# Sheet1.net
KiCad netlist of a schematic drawn in Altium Designer
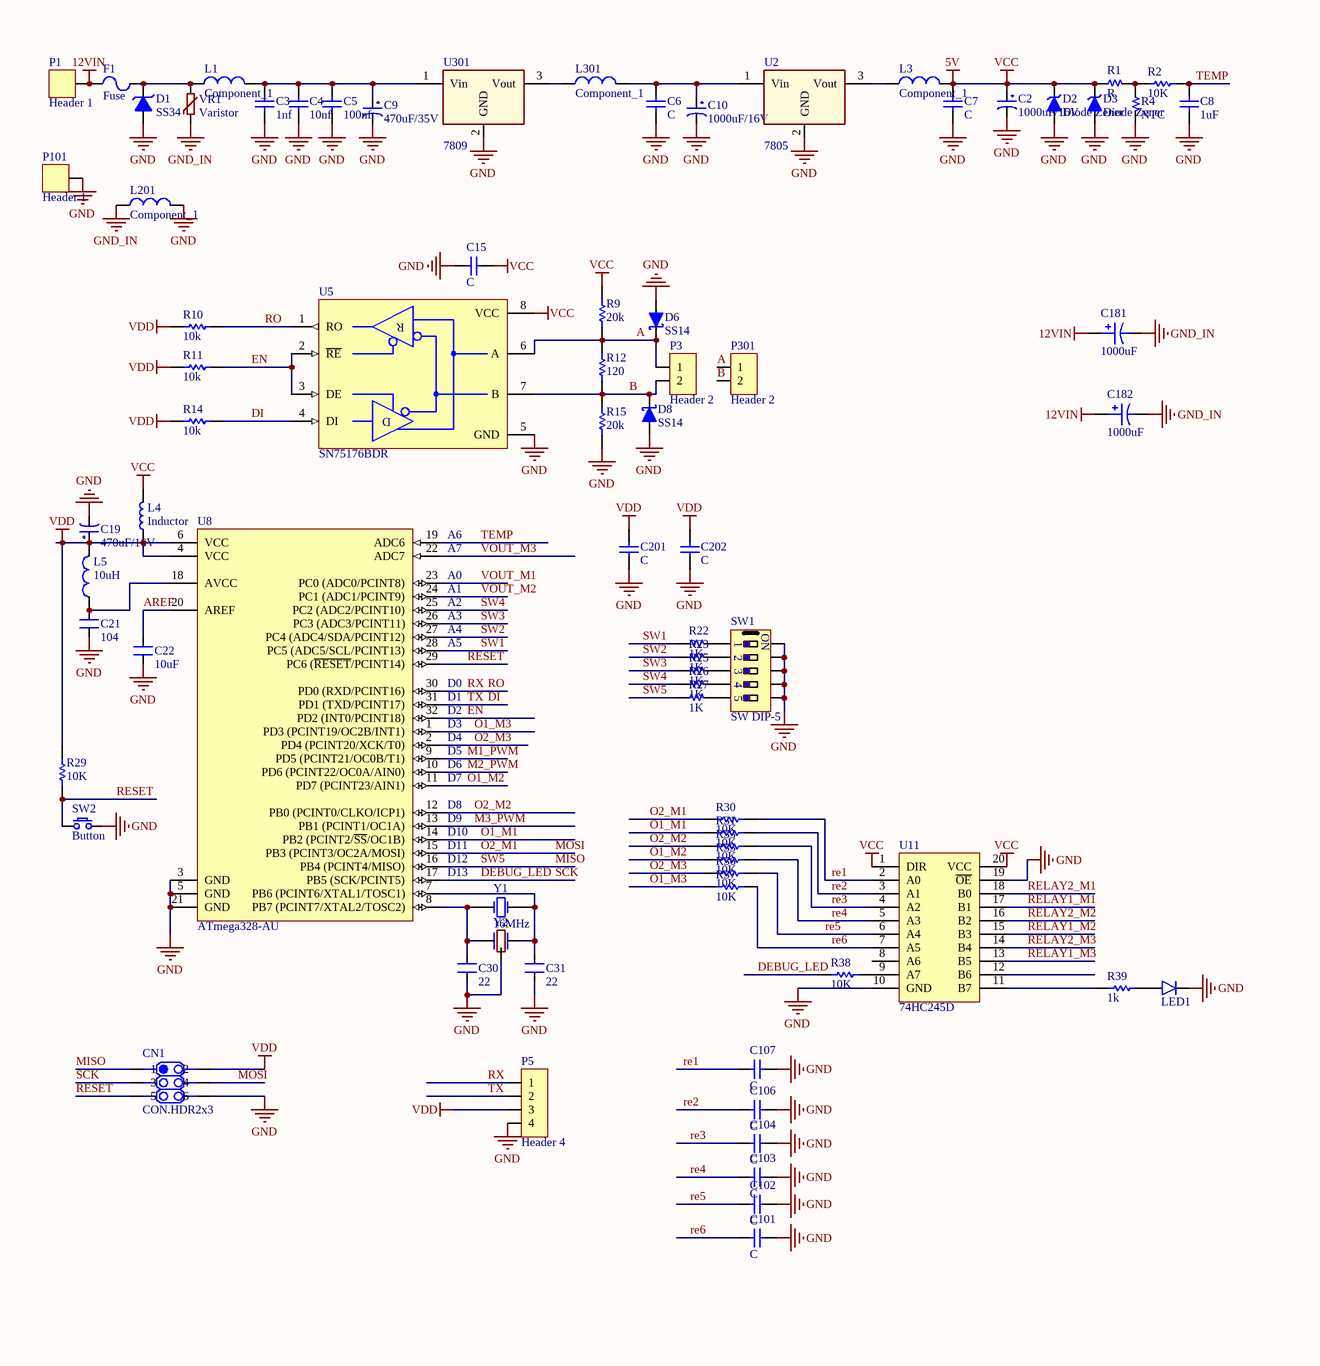
[diagram p0: Sheet1.SchDoc, left]
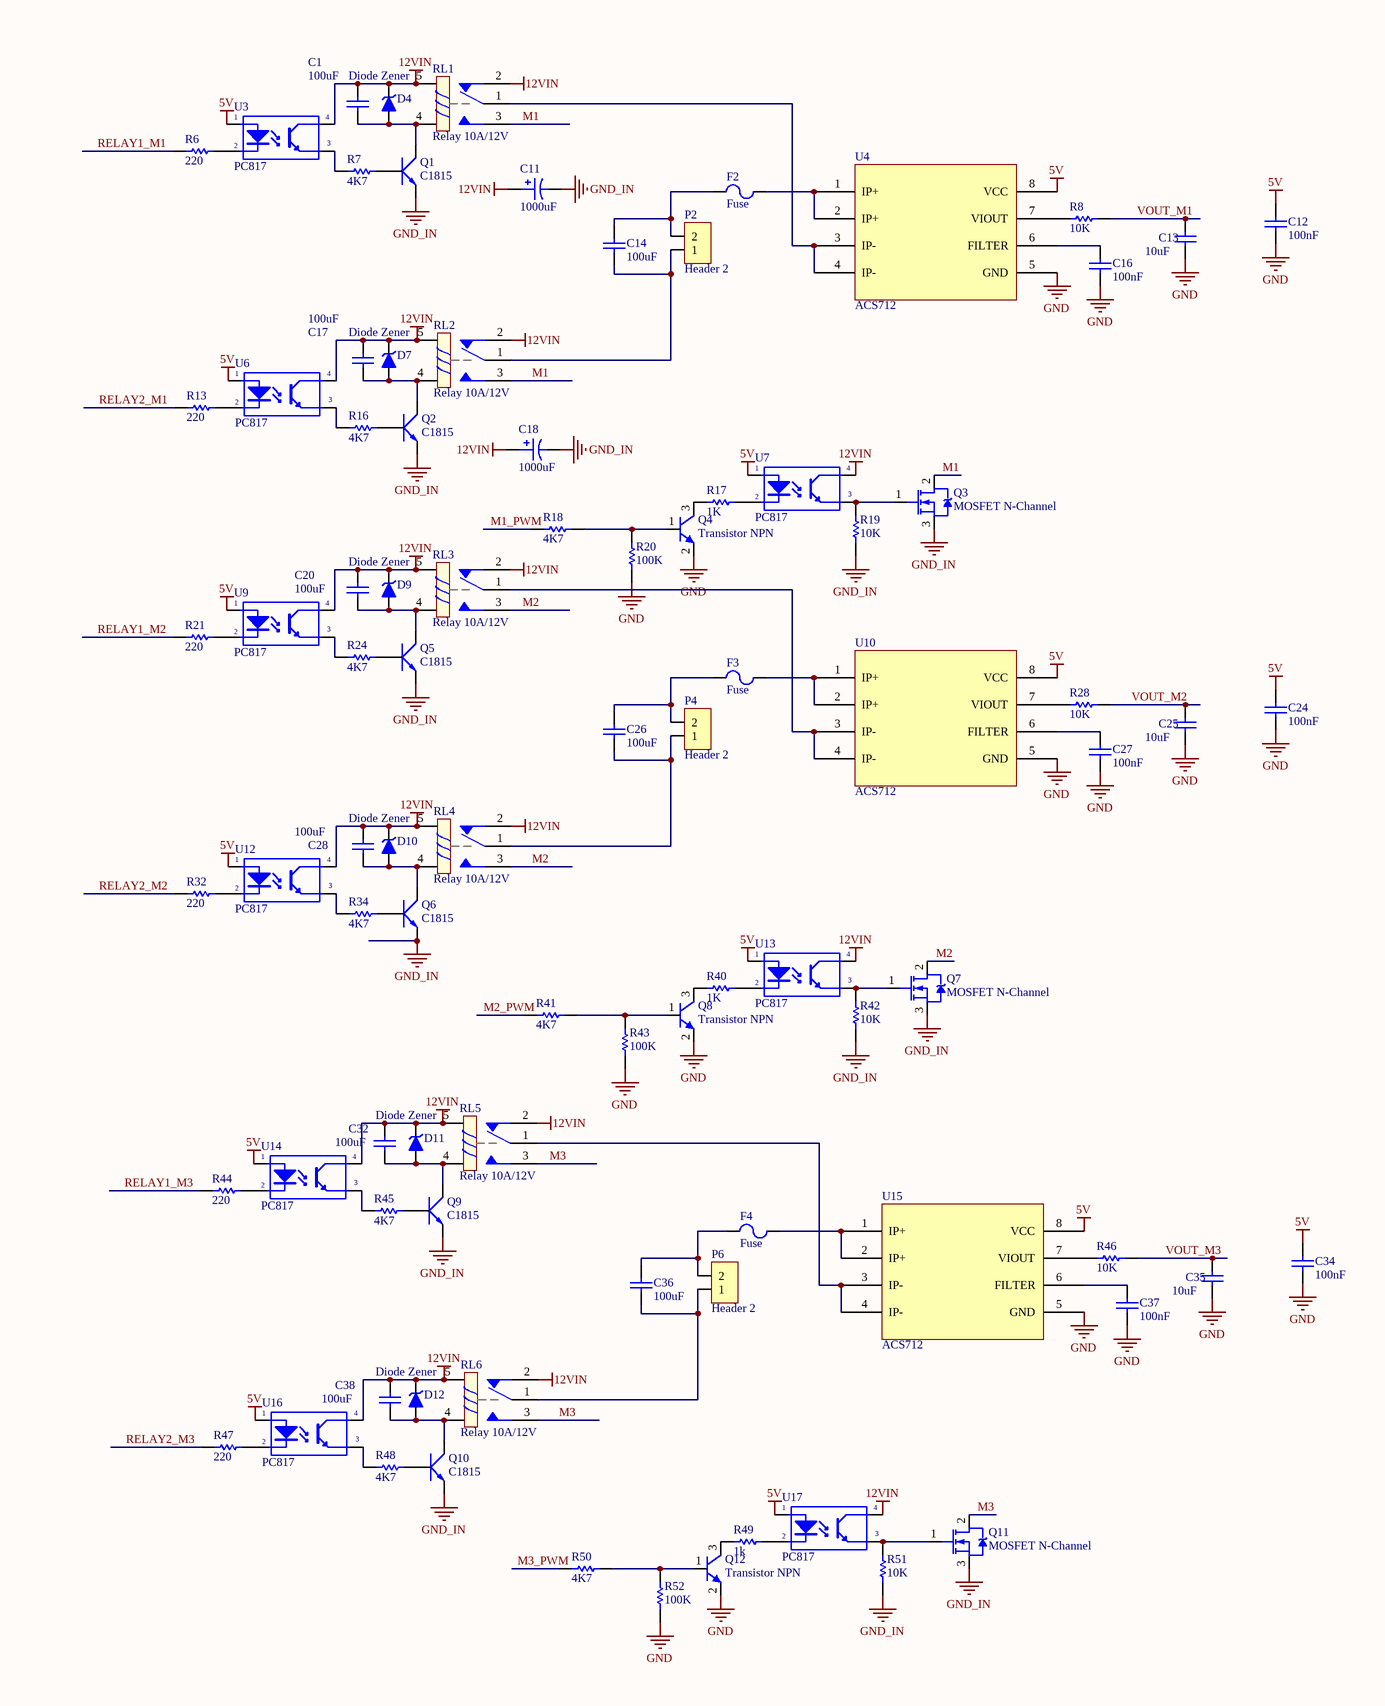
[diagram p1: Sheet1.SchDoc, right]

(export (version "E")
  (design (tool "Eeschema 10.0.6"))
  (components
    (comp (ref "C1")
      (value "100uF")
      (footprint "C 0805 (2012)")
      (description "Non-polarized Capacitor")
      (fields (field (name "Comment") "Cap Non-pol") (field (name "PUBLISHER") "Altium Limited"))
      (libsource (lib "phong") (part "Cap Non-pol"))
    )
    (comp (ref "C2")
      (value "1000uF/16V")
      (footprint "WCAP-PSHP 8x8.7x3.1")
      (description "Cap 1000uF/16V - 220uF/50V")
      (libsource (lib "syhaunguyen") (part "CP4"))
    )
    (comp (ref "C3")
      (value "1nf")
      (footprint "C 0805 (2012)")
      (description "Capacitor non-pol")
      (libsource (lib "BKIT4U_LIB") (part "Capacitor NP"))
    )
    (comp (ref "C4")
      (value "10nf")
      (footprint "C 0805 (2012)")
      (description "Capacitor non-pol")
      (libsource (lib "BKIT4U_LIB") (part "Capacitor NP"))
    )
    (comp (ref "C5")
      (value "100nf")
      (footprint "C 0805 (2012)")
      (description "Capacitor non-pol")
      (libsource (lib "BKIT4U_LIB") (part "Capacitor NP"))
    )
    (comp (ref "C6")
      (value "C")
      (footprint "C 0805 (2012)")
      (description "Capacitor non-pol")
      (libsource (lib "BKIT4U_LIB") (part "Capacitor NP"))
    )
    (comp (ref "C7")
      (value "C")
      (footprint "C 0805 (2012)")
      (description "Capacitor non-pol")
      (libsource (lib "BKIT4U_LIB") (part "Capacitor NP"))
    )
    (comp (ref "C8")
      (value "1uF")
      (footprint "C 0805 (2012)")
      (description "Capacitor non-pol")
      (libsource (lib "BKIT4U_LIB") (part "Capacitor NP"))
    )
    (comp (ref "C9")
      (value "470uF/35V")
      (footprint "WCAP-PSHP 8x8.7x3.1")
      (description "Cap 100uF/35V - 470uF/16V")
      (libsource (lib "syhaunguyen") (part "CP3"))
    )
    (comp (ref "C10")
      (value "1000uF/16V")
      (footprint "WCAP-PSHP 8x8.7x3.1")
      (description "Cap 1000uF/16V - 220uF/50V")
      (libsource (lib "syhaunguyen") (part "CP4"))
    )
    (comp (ref "C11")
      (value "1000uF")
      (footprint "RADIAL E")
      (description "Polarized Capacitor")
      (fields (field (name "Comment") "Cap Pol") (field (name "PUBLISHER") "Altium Limited"))
      (libsource (lib "phong") (part "Cap Pol"))
    )
    (comp (ref "C12")
      (value "100nF")
      (footprint "C 0805 (2012)")
      (description "Non-polarized Capacitor")
      (fields (field (name "Comment") "Cap Non-pol") (field (name "PUBLISHER") "Altium Limited"))
      (libsource (lib "phong") (part "Cap Non-pol"))
    )
    (comp (ref "C13")
      (value "10uF")
      (footprint "C 0805 (2012)")
      (description "Non-polarized Capacitor")
      (fields (field (name "Comment") "Cap Non-pol") (field (name "PUBLISHER") "Altium Limited"))
      (libsource (lib "phong") (part "Cap Non-pol"))
    )
    (comp (ref "C14")
      (value "100uF")
      (footprint "Cap Non-Pol 5mm")
      (description "Non-polarized Capacitor")
      (fields (field (name "Comment") "Cap Non-pol") (field (name "PUBLISHER") "Altium Limited"))
      (libsource (lib "phong") (part "Cap Non-pol"))
    )
    (comp (ref "C15")
      (value "C")
      (footprint "C 0805 (2012)")
      (description "Capacitor non-pol")
      (libsource (lib "BKIT4U_LIB") (part "Capacitor NP"))
    )
    (comp (ref "C16")
      (value "100nF")
      (footprint "C 0805 (2012)")
      (description "Non-polarized Capacitor")
      (fields (field (name "Comment") "Cap Non-pol") (field (name "PUBLISHER") "Altium Limited"))
      (libsource (lib "phong") (part "Cap Non-pol"))
    )
    (comp (ref "C17")
      (value "100uF")
      (footprint "C 0805 (2012)")
      (description "Non-polarized Capacitor")
      (fields (field (name "Comment") "Cap Non-pol") (field (name "PUBLISHER") "Altium Limited"))
      (libsource (lib "phong") (part "Cap Non-pol"))
    )
    (comp (ref "C18")
      (value "1000uF")
      (footprint "RADIAL E")
      (description "Polarized Capacitor")
      (fields (field (name "Comment") "Cap Pol") (field (name "PUBLISHER") "Altium Limited"))
      (libsource (lib "phong") (part "Cap Pol"))
    )
    (comp (ref "C19")
      (value "470uF/16V")
      (footprint "WCAP-PSHP 8x8.7x3.1")
      (description "Cap 1000uF/16V - 220uF/50V")
      (libsource (lib "syhaunguyen") (part "CP4"))
    )
    (comp (ref "C20")
      (value "100uF")
      (footprint "C 0805 (2012)")
      (description "Non-polarized Capacitor")
      (fields (field (name "Comment") "Cap Non-pol") (field (name "PUBLISHER") "Altium Limited"))
      (libsource (lib "phong") (part "Cap Non-pol"))
    )
    (comp (ref "C21")
      (value "104")
      (footprint "R 0805 (2012)")
      (description "Cap np 104 => 105pF")
      (libsource (lib "syhaunguyen") (part "CN2"))
    )
    (comp (ref "C22")
      (value "10uF")
      (footprint "R 0805 (2012)")
      (description "Cap np  1pF - 472pF")
      (libsource (lib "syhaunguyen") (part "CN1"))
    )
    (comp (ref "C24")
      (value "100nF")
      (footprint "C 0805 (2012)")
      (description "Non-polarized Capacitor")
      (fields (field (name "Comment") "Cap Non-pol") (field (name "PUBLISHER") "Altium Limited"))
      (libsource (lib "phong") (part "Cap Non-pol"))
    )
    (comp (ref "C25")
      (value "10uF")
      (footprint "C 0805 (2012)")
      (description "Non-polarized Capacitor")
      (fields (field (name "Comment") "Cap Non-pol") (field (name "PUBLISHER") "Altium Limited"))
      (libsource (lib "phong") (part "Cap Non-pol"))
    )
    (comp (ref "C26")
      (value "100uF")
      (footprint "Cap Non-Pol 5mm")
      (description "Non-polarized Capacitor")
      (fields (field (name "Comment") "Cap Non-pol") (field (name "PUBLISHER") "Altium Limited"))
      (libsource (lib "phong") (part "Cap Non-pol"))
    )
    (comp (ref "C27")
      (value "100nF")
      (footprint "C 0805 (2012)")
      (description "Non-polarized Capacitor")
      (fields (field (name "Comment") "Cap Non-pol") (field (name "PUBLISHER") "Altium Limited"))
      (libsource (lib "phong") (part "Cap Non-pol"))
    )
    (comp (ref "C28")
      (value "100uF")
      (footprint "C 0805 (2012)")
      (description "Non-polarized Capacitor")
      (fields (field (name "Comment") "Cap Non-pol") (field (name "PUBLISHER") "Altium Limited"))
      (libsource (lib "phong") (part "Cap Non-pol"))
    )
    (comp (ref "C30")
      (value "22")
      (footprint "C 0805 (2012)")
      (description "Cap np 104 => 105pF")
      (libsource (lib "syhaunguyen") (part "CN2"))
    )
    (comp (ref "C31")
      (value "22")
      (footprint "C 0805 (2012)")
      (description "Cap np 104 => 105pF")
      (libsource (lib "syhaunguyen") (part "CN2"))
    )
    (comp (ref "C32")
      (value "100uF")
      (footprint "C 0805 (2012)")
      (description "Non-polarized Capacitor")
      (fields (field (name "Comment") "Cap Non-pol") (field (name "PUBLISHER") "Altium Limited"))
      (libsource (lib "phong") (part "Cap Non-pol"))
    )
    (comp (ref "C34")
      (value "100nF")
      (footprint "Cap Non-Pol 5mm")
      (description "Non-polarized Capacitor")
      (fields (field (name "Comment") "Cap Non-pol") (field (name "PUBLISHER") "Altium Limited"))
      (libsource (lib "phong") (part "Cap Non-pol"))
    )
    (comp (ref "C35")
      (value "10uF")
      (footprint "C 0805 (2012)")
      (description "Non-polarized Capacitor")
      (fields (field (name "Comment") "Cap Non-pol") (field (name "PUBLISHER") "Altium Limited"))
      (libsource (lib "phong") (part "Cap Non-pol"))
    )
    (comp (ref "C36")
      (value "100uF")
      (footprint "Cap Non-Pol 5mm")
      (description "Non-polarized Capacitor")
      (fields (field (name "Comment") "Cap Non-pol") (field (name "PUBLISHER") "Altium Limited"))
      (libsource (lib "phong") (part "Cap Non-pol"))
    )
    (comp (ref "C37")
      (value "100nF")
      (footprint "C 0805 (2012)")
      (description "Non-polarized Capacitor")
      (fields (field (name "Comment") "Cap Non-pol") (field (name "PUBLISHER") "Altium Limited"))
      (libsource (lib "phong") (part "Cap Non-pol"))
    )
    (comp (ref "C38")
      (value "100uF")
      (footprint "C 0805 (2012)")
      (description "Non-polarized Capacitor")
      (fields (field (name "Comment") "Cap Non-pol") (field (name "PUBLISHER") "Altium Limited"))
      (libsource (lib "phong") (part "Cap Non-pol"))
    )
    (comp (ref "C101")
      (value "C")
      (footprint "C 0805")
      (description "Capacitor non-pol")
      (libsource (lib "chipfc_altium_libs") (part "Capacitor NP"))
    )
    (comp (ref "C102")
      (value "C")
      (footprint "C 0805")
      (description "Capacitor non-pol")
      (libsource (lib "chipfc_altium_libs") (part "Capacitor NP"))
    )
    (comp (ref "C103")
      (value "C")
      (footprint "C 0805")
      (description "Capacitor non-pol")
      (libsource (lib "chipfc_altium_libs") (part "Capacitor NP"))
    )
    (comp (ref "C104")
      (value "C")
      (footprint "C 0805")
      (description "Capacitor non-pol")
      (libsource (lib "chipfc_altium_libs") (part "Capacitor NP"))
    )
    (comp (ref "C106")
      (value "C")
      (footprint "C 0805")
      (description "Capacitor non-pol")
      (libsource (lib "chipfc_altium_libs") (part "Capacitor NP"))
    )
    (comp (ref "C107")
      (value "C")
      (footprint "C 0805")
      (description "Capacitor non-pol")
      (libsource (lib "chipfc_altium_libs") (part "Capacitor NP"))
    )
    (comp (ref "C181")
      (value "1000uF")
      (footprint "RADIAL E")
      (description "Polarized Capacitor")
      (fields (field (name "Comment") "Cap Pol") (field (name "PUBLISHER") "Altium Limited"))
      (libsource (lib "phong") (part "Cap Pol"))
    )
    (comp (ref "C182")
      (value "1000uF")
      (footprint "RADIAL E")
      (description "Polarized Capacitor")
      (fields (field (name "Comment") "Cap Pol") (field (name "PUBLISHER") "Altium Limited"))
      (libsource (lib "phong") (part "Cap Pol"))
    )
    (comp (ref "C201")
      (value "C")
      (footprint "C 0805 (2012)")
      (description "Capacitor non-pol")
      (libsource (lib "BKIT4U_LIB") (part "Capacitor NP"))
    )
    (comp (ref "C202")
      (value "C")
      (footprint "C 0805 (2012)")
      (description "Capacitor non-pol")
      (libsource (lib "BKIT4U_LIB") (part "Capacitor NP"))
    )
    (comp (ref "CN1")
      (value "CON.HDR2x3")
      (footprint "Header 3x2")
      (description "Header 2x3")
      (fields (field (name "PUBLISHER") "Hoang Nguyen"))
      (libsource (lib "phong") (part "CON.HDR2x3"))
    )
    (comp (ref "D1")
      (value "SS34")
      (footprint "DO-214AC (SMA)")
      (libsource (lib "syhaunguyen") (part "Zener"))
    )
    (comp (ref "D2")
      (value "Diode Zener")
      (footprint "SOD-80")
      (description "Zener Diode")
      (fields (field (name "PUBLISHER") "Altium Limited"))
      (libsource (lib "BKIT4U_LIB") (part "Diode Zener"))
    )
    (comp (ref "D3")
      (value "Diode Zener")
      (footprint "SOD-80")
      (description "Zener Diode")
      (fields (field (name "PUBLISHER") "Altium Limited"))
      (libsource (lib "BKIT4U_LIB") (part "Diode Zener"))
    )
    (comp (ref "D4")
      (value "Diode Zener")
      (footprint "SOD-80")
      (description "Zener Diode")
      (fields (field (name "PUBLISHER") "Altium Limited"))
      (libsource (lib "BKIT4U_LIB") (part "Diode Zener"))
    )
    (comp (ref "D6")
      (value "SS14")
      (footprint "DO-214AC (SMA)")
      (description "Schottky Diode")
      (fields (field (name "PUBLISHER") "Altium Limited"))
      (libsource (lib "BKIT4U_LIB") (part "Diode Schottky"))
    )
    (comp (ref "D7")
      (value "Diode Zener")
      (footprint "SOD-80")
      (description "Zener Diode")
      (fields (field (name "PUBLISHER") "Altium Limited"))
      (libsource (lib "BKIT4U_LIB") (part "Diode Zener"))
    )
    (comp (ref "D8")
      (value "SS14")
      (footprint "DO-214AC (SMA)")
      (description "Schottky Diode")
      (fields (field (name "PUBLISHER") "Altium Limited"))
      (libsource (lib "BKIT4U_LIB") (part "Diode Schottky"))
    )
    (comp (ref "D9")
      (value "Diode Zener")
      (footprint "SOD-80")
      (description "Zener Diode")
      (fields (field (name "PUBLISHER") "Altium Limited"))
      (libsource (lib "BKIT4U_LIB") (part "Diode Zener"))
    )
    (comp (ref "D10")
      (value "Diode Zener")
      (footprint "SOD-80")
      (description "Zener Diode")
      (fields (field (name "PUBLISHER") "Altium Limited"))
      (libsource (lib "BKIT4U_LIB") (part "Diode Zener"))
    )
    (comp (ref "D11")
      (value "Diode Zener")
      (footprint "SOD-80")
      (description "Zener Diode")
      (fields (field (name "PUBLISHER") "Altium Limited"))
      (libsource (lib "BKIT4U_LIB") (part "Diode Zener"))
    )
    (comp (ref "D12")
      (value "Diode Zener")
      (footprint "SOD-80")
      (description "Zener Diode")
      (fields (field (name "PUBLISHER") "Altium Limited"))
      (libsource (lib "BKIT4U_LIB") (part "Diode Zener"))
    )
    (comp (ref "F1")
      (value "Fuse")
      (footprint "FUSE 4 DIP")
      (libsource (lib "chipfc_altium_libs") (part "Fuse"))
    )
    (comp (ref "F2")
      (value "Fuse")
      (footprint "FUSE 4 DIP")
      (libsource (lib "chipfc_altium_libs") (part "Fuse"))
    )
    (comp (ref "F3")
      (value "Fuse")
      (footprint "FUSE 4 DIP")
      (libsource (lib "chipfc_altium_libs") (part "Fuse"))
    )
    (comp (ref "F4")
      (value "Fuse")
      (footprint "FUSE 4 DIP")
      (libsource (lib "chipfc_altium_libs") (part "Fuse"))
    )
    (comp (ref "L1")
      (value "Component_1")
      (footprint "1210")
      (libsource (lib "Integrated_Library1") (part "Component_1"))
    )
    (comp (ref "L3")
      (value "Component_1")
      (footprint "1210")
      (libsource (lib "Integrated_Library1") (part "Component_1"))
    )
    (comp (ref "L4")
      (value "Inductor")
      (footprint "Inductor SMD 4.8x4.8")
      (libsource (lib "BKIT4U_LIB") (part "Inductor"))
    )
    (comp (ref "L5")
      (value "10uH")
      (footprint "R 0805 (2012)")
      (description "Inductor")
      (libsource (lib "syhaunguyen") (part "L1"))
    )
    (comp (ref "L201")
      (value "Component_1")
      (footprint "1210")
      (libsource (lib "Integrated_Library1") (part "Component_1"))
    )
    (comp (ref "L301")
      (value "Component_1")
      (footprint "1210")
      (libsource (lib "Integrated_Library1") (part "Component_1"))
    )
    (comp (ref "LED1")
      (value "Led")
      (footprint "Led SMD 0805")
      (description "Typical LED")
      (libsource (lib "BKIT4U_LIB") (part "Led"))
    )
    (comp (ref "P1")
      (value "Header 1")
      (footprint "HDR/Terminal/1/copper/8.8")
      (description "Header, 1-Pin")
      (libsource (lib "chipfc_altium_libs") (part "Header 1"))
    )
    (comp (ref "P2")
      (value "Header 2")
      (footprint "HDR Domino 2")
      (description "Header, 2-Pin")
      (fields (field (name "PUBLISHER") "Altium Limited"))
      (libsource (lib "BKIT4U_LIB") (part "Header 2"))
    )
    (comp (ref "P3")
      (value "Header 2")
      (footprint "HDR Domino 2")
      (description "Header, 2-Pin")
      (fields (field (name "PUBLISHER") "Altium Limited"))
      (libsource (lib "") (part "Header 2_1"))
    )
    (comp (ref "P4")
      (value "Header 2")
      (footprint "HDR Domino 2")
      (description "Header, 2-Pin")
      (fields (field (name "PUBLISHER") "Altium Limited"))
      (libsource (lib "BKIT4U_LIB") (part "Header 2"))
    )
    (comp (ref "P5")
      (value "Header 4")
      (footprint "Header 4")
      (description "Header, 4-Pin")
      (libsource (lib "BKIT4U_LIB") (part "Header 4"))
    )
    (comp (ref "P6")
      (value "Header 2")
      (footprint "HDR Domino 2")
      (description "Header, 2-Pin")
      (fields (field (name "PUBLISHER") "Altium Limited"))
      (libsource (lib "BKIT4U_LIB") (part "Header 2"))
    )
    (comp (ref "P101")
      (value "Header 1")
      (footprint "HDR/Terminal/1/copper/8.8")
      (description "Header, 1-Pin")
      (libsource (lib "chipfc_altium_libs") (part "Header 1"))
    )
    (comp (ref "P301")
      (value "Header 2")
      (footprint "HDR Domino 2")
      (description "Header, 2-Pin")
      (fields (field (name "PUBLISHER") "Altium Limited"))
      (libsource (lib "") (part "Header 2_1"))
    )
    (comp (ref "Q1")
      (value "C1815")
      (footprint "SOT23B")
      (description "NPN 600mW, ECB")
      (libsource (lib "syhaunguyen") (part "C1815"))
    )
    (comp (ref "Q2")
      (value "C1815")
      (footprint "SOT23B")
      (description "NPN 600mW, ECB")
      (libsource (lib "syhaunguyen") (part "C1815"))
    )
    (comp (ref "Q3")
      (value "MOSFET N-Channel")
      (footprint "TO-252 (DPAK)")
      (libsource (lib "BKIT4U_LIB") (part "MOSFET N-Channel"))
    )
    (comp (ref "Q4")
      (value "Transistor NPN")
      (footprint "SOT-23")
      (description "NPN Bipolar Transistor")
      (libsource (lib "BKIT4U_LIB") (part "Transistor NPN"))
    )
    (comp (ref "Q5")
      (value "C1815")
      (footprint "SOT23B")
      (description "NPN 600mW, ECB")
      (libsource (lib "syhaunguyen") (part "C1815"))
    )
    (comp (ref "Q6")
      (value "C1815")
      (footprint "SOT23B")
      (description "NPN 600mW, ECB")
      (libsource (lib "syhaunguyen") (part "C1815"))
    )
    (comp (ref "Q7")
      (value "MOSFET N-Channel")
      (footprint "TO-252 (DPAK)")
      (libsource (lib "BKIT4U_LIB") (part "MOSFET N-Channel"))
    )
    (comp (ref "Q8")
      (value "Transistor NPN")
      (footprint "SOT-23")
      (description "NPN Bipolar Transistor")
      (libsource (lib "BKIT4U_LIB") (part "Transistor NPN"))
    )
    (comp (ref "Q9")
      (value "C1815")
      (footprint "SOT23B")
      (description "NPN 600mW, ECB")
      (libsource (lib "syhaunguyen") (part "C1815"))
    )
    (comp (ref "Q10")
      (value "C1815")
      (footprint "SOT23B")
      (description "NPN 600mW, ECB")
      (libsource (lib "syhaunguyen") (part "C1815"))
    )
    (comp (ref "Q11")
      (value "MOSFET N-Channel")
      (footprint "TO-252 (DPAK)")
      (libsource (lib "BKIT4U_LIB") (part "MOSFET N-Channel"))
    )
    (comp (ref "Q12")
      (value "Transistor NPN")
      (footprint "SOT-23")
      (description "NPN Bipolar Transistor")
      (libsource (lib "BKIT4U_LIB") (part "Transistor NPN"))
    )
    (comp (ref "R1")
      (value "R")
      (footprint "R 0805")
      (description "Resistor")
      (libsource (lib "chipfc_altium_libs") (part "Resistor"))
    )
    (comp (ref "R2")
      (value "10K")
      (footprint "R 0805 (2012)")
      (description "Resistor")
      (fields (field (name "PUBLISHER") "Altium Limited"))
      (libsource (lib "BKIT4U_LIB") (part "Resistor"))
    )
    (comp (ref "R4")
      (value "NTC")
      (footprint "R 1/4W/300")
      (description "Resistor")
      (libsource (lib "chipfc_altium_libs") (part "Resistor"))
    )
    (comp (ref "R6")
      (value "220")
      (footprint "R 0805 (2012)")
      (description "Resistor")
      (fields (field (name "PUBLISHER") "Altium Limited"))
      (libsource (lib "BKIT4U_LIB") (part "Resistor"))
    )
    (comp (ref "R7")
      (value "4K7")
      (footprint "R 0805 (2012)")
      (description "Resistor")
      (fields (field (name "PUBLISHER") "Altium Limited"))
      (libsource (lib "BKIT4U_LIB") (part "Resistor"))
    )
    (comp (ref "R8")
      (value "10K")
      (footprint "R 0805 (2012)")
      (description "Resistor")
      (fields (field (name "PUBLISHER") "Altium Limited"))
      (libsource (lib "BKIT4U_LIB") (part "Resistor"))
    )
    (comp (ref "R9")
      (value "20k")
      (footprint "R 0805 (2012)")
      (description "Resistor")
      (fields (field (name "PUBLISHER") "Altium Limited"))
      (libsource (lib "BKIT4U_LIB") (part "Resistor"))
    )
    (comp (ref "R10")
      (value "10k")
      (footprint "R 0805 (2012)")
      (description "Resistor")
      (fields (field (name "PUBLISHER") "Altium Limited"))
      (libsource (lib "BKIT4U_LIB") (part "Resistor"))
    )
    (comp (ref "R11")
      (value "10k")
      (footprint "R 0805 (2012)")
      (description "Resistor")
      (fields (field (name "PUBLISHER") "Altium Limited"))
      (libsource (lib "BKIT4U_LIB") (part "Resistor"))
    )
    (comp (ref "R12")
      (value "120")
      (footprint "R 0805 (2012)")
      (description "Resistor")
      (fields (field (name "PUBLISHER") "Altium Limited"))
      (libsource (lib "BKIT4U_LIB") (part "Resistor"))
    )
    (comp (ref "R13")
      (value "220")
      (footprint "R 0805 (2012)")
      (description "Resistor")
      (fields (field (name "PUBLISHER") "Altium Limited"))
      (libsource (lib "BKIT4U_LIB") (part "Resistor"))
    )
    (comp (ref "R14")
      (value "10k")
      (footprint "R 0805 (2012)")
      (description "Resistor")
      (fields (field (name "PUBLISHER") "Altium Limited"))
      (libsource (lib "BKIT4U_LIB") (part "Resistor"))
    )
    (comp (ref "R15")
      (value "20k")
      (footprint "R 0805 (2012)")
      (description "Resistor")
      (fields (field (name "PUBLISHER") "Altium Limited"))
      (libsource (lib "BKIT4U_LIB") (part "Resistor"))
    )
    (comp (ref "R16")
      (value "4K7")
      (footprint "R 0805 (2012)")
      (description "Resistor")
      (fields (field (name "PUBLISHER") "Altium Limited"))
      (libsource (lib "BKIT4U_LIB") (part "Resistor"))
    )
    (comp (ref "R17")
      (value "1K")
      (footprint "R 0805 (2012)")
      (description "Resistor")
      (fields (field (name "PUBLISHER") "Altium Limited"))
      (libsource (lib "BKIT4U_LIB") (part "Resistor"))
    )
    (comp (ref "R18")
      (value "4K7")
      (footprint "R 0805 (2012)")
      (description "Resistor")
      (fields (field (name "PUBLISHER") "Altium Limited"))
      (libsource (lib "BKIT4U_LIB") (part "Resistor"))
    )
    (comp (ref "R19")
      (value "10K")
      (footprint "R 0805 (2012)")
      (description "Resistor")
      (fields (field (name "PUBLISHER") "Altium Limited"))
      (libsource (lib "BKIT4U_LIB") (part "Resistor"))
    )
    (comp (ref "R20")
      (value "100K")
      (footprint "R 0805 (2012)")
      (description "Resistor")
      (fields (field (name "PUBLISHER") "Altium Limited"))
      (libsource (lib "BKIT4U_LIB") (part "Resistor"))
    )
    (comp (ref "R21")
      (value "220")
      (footprint "R 0805 (2012)")
      (description "Resistor")
      (fields (field (name "PUBLISHER") "Altium Limited"))
      (libsource (lib "BKIT4U_LIB") (part "Resistor"))
    )
    (comp (ref "R22")
      (value "1K")
      (footprint "R 0805")
      (description "Resistor")
      (libsource (lib "chipfc_altium_libs") (part "Resistor"))
    )
    (comp (ref "R23")
      (value "1K")
      (footprint "R 0805")
      (description "Resistor")
      (libsource (lib "chipfc_altium_libs") (part "Resistor"))
    )
    (comp (ref "R24")
      (value "4K7")
      (footprint "R 0805 (2012)")
      (description "Resistor")
      (fields (field (name "PUBLISHER") "Altium Limited"))
      (libsource (lib "BKIT4U_LIB") (part "Resistor"))
    )
    (comp (ref "R25")
      (value "1K")
      (footprint "R 0805")
      (description "Resistor")
      (libsource (lib "chipfc_altium_libs") (part "Resistor"))
    )
    (comp (ref "R26")
      (value "1K")
      (footprint "R 0805")
      (description "Resistor")
      (libsource (lib "chipfc_altium_libs") (part "Resistor"))
    )
    (comp (ref "R27")
      (value "1K")
      (footprint "R 0805")
      (description "Resistor")
      (libsource (lib "chipfc_altium_libs") (part "Resistor"))
    )
    (comp (ref "R28")
      (value "10K")
      (footprint "R 0805 (2012)")
      (description "Resistor")
      (fields (field (name "PUBLISHER") "Altium Limited"))
      (libsource (lib "BKIT4U_LIB") (part "Resistor"))
    )
    (comp (ref "R29")
      (value "10K")
      (footprint "R 0805 (2012)")
      (description "Resistor")
      (fields (field (name "PUBLISHER") "Altium Limited"))
      (libsource (lib "phong") (part "Resistor"))
    )
    (comp (ref "R30")
      (value "10K")
      (footprint "R 0805 (2012)")
      (description "Resistor")
      (fields (field (name "PUBLISHER") "Altium Limited"))
      (libsource (lib "BKIT4U_LIB") (part "Resistor"))
    )
    (comp (ref "R31")
      (value "10K")
      (footprint "R 0805 (2012)")
      (description "Resistor")
      (fields (field (name "PUBLISHER") "Altium Limited"))
      (libsource (lib "BKIT4U_LIB") (part "Resistor"))
    )
    (comp (ref "R32")
      (value "220")
      (footprint "R 0805 (2012)")
      (description "Resistor")
      (fields (field (name "PUBLISHER") "Altium Limited"))
      (libsource (lib "BKIT4U_LIB") (part "Resistor"))
    )
    (comp (ref "R33")
      (value "10K")
      (footprint "R 0805 (2012)")
      (description "Resistor")
      (fields (field (name "PUBLISHER") "Altium Limited"))
      (libsource (lib "BKIT4U_LIB") (part "Resistor"))
    )
    (comp (ref "R34")
      (value "4K7")
      (footprint "R 0805 (2012)")
      (description "Resistor")
      (fields (field (name "PUBLISHER") "Altium Limited"))
      (libsource (lib "BKIT4U_LIB") (part "Resistor"))
    )
    (comp (ref "R35")
      (value "10K")
      (footprint "R 0805 (2012)")
      (description "Resistor")
      (fields (field (name "PUBLISHER") "Altium Limited"))
      (libsource (lib "BKIT4U_LIB") (part "Resistor"))
    )
    (comp (ref "R36")
      (value "10K")
      (footprint "R 0805 (2012)")
      (description "Resistor")
      (fields (field (name "PUBLISHER") "Altium Limited"))
      (libsource (lib "BKIT4U_LIB") (part "Resistor"))
    )
    (comp (ref "R37")
      (value "10K")
      (footprint "R 0805 (2012)")
      (description "Resistor")
      (fields (field (name "PUBLISHER") "Altium Limited"))
      (libsource (lib "BKIT4U_LIB") (part "Resistor"))
    )
    (comp (ref "R38")
      (value "10K")
      (footprint "R 0805 (2012)")
      (description "Resistor")
      (fields (field (name "PUBLISHER") "Altium Limited"))
      (libsource (lib "BKIT4U_LIB") (part "Resistor"))
    )
    (comp (ref "R39")
      (value "1k")
      (footprint "R 0805 (2012)")
      (description "Resistor")
      (fields (field (name "PUBLISHER") "Altium Limited"))
      (libsource (lib "BKIT4U_LIB") (part "Resistor"))
    )
    (comp (ref "R40")
      (value "1K")
      (footprint "R 0805 (2012)")
      (description "Resistor")
      (fields (field (name "PUBLISHER") "Altium Limited"))
      (libsource (lib "BKIT4U_LIB") (part "Resistor"))
    )
    (comp (ref "R41")
      (value "4K7")
      (footprint "R 0805 (2012)")
      (description "Resistor")
      (fields (field (name "PUBLISHER") "Altium Limited"))
      (libsource (lib "BKIT4U_LIB") (part "Resistor"))
    )
    (comp (ref "R42")
      (value "10K")
      (footprint "R 0805 (2012)")
      (description "Resistor")
      (fields (field (name "PUBLISHER") "Altium Limited"))
      (libsource (lib "BKIT4U_LIB") (part "Resistor"))
    )
    (comp (ref "R43")
      (value "100K")
      (footprint "R 0805 (2012)")
      (description "Resistor")
      (fields (field (name "PUBLISHER") "Altium Limited"))
      (libsource (lib "BKIT4U_LIB") (part "Resistor"))
    )
    (comp (ref "R44")
      (value "220")
      (footprint "R 0805 (2012)")
      (description "Resistor")
      (fields (field (name "PUBLISHER") "Altium Limited"))
      (libsource (lib "BKIT4U_LIB") (part "Resistor"))
    )
    (comp (ref "R45")
      (value "4K7")
      (footprint "R 0805 (2012)")
      (description "Resistor")
      (fields (field (name "PUBLISHER") "Altium Limited"))
      (libsource (lib "BKIT4U_LIB") (part "Resistor"))
    )
    (comp (ref "R46")
      (value "10K")
      (footprint "R 0805 (2012)")
      (description "Resistor")
      (fields (field (name "PUBLISHER") "Altium Limited"))
      (libsource (lib "BKIT4U_LIB") (part "Resistor"))
    )
    (comp (ref "R47")
      (value "220")
      (footprint "R 0805 (2012)")
      (description "Resistor")
      (fields (field (name "PUBLISHER") "Altium Limited"))
      (libsource (lib "BKIT4U_LIB") (part "Resistor"))
    )
    (comp (ref "R48")
      (value "4K7")
      (footprint "R 0805 (2012)")
      (description "Resistor")
      (fields (field (name "PUBLISHER") "Altium Limited"))
      (libsource (lib "BKIT4U_LIB") (part "Resistor"))
    )
    (comp (ref "R49")
      (value "1k")
      (footprint "R 0805 (2012)")
      (description "Resistor")
      (fields (field (name "PUBLISHER") "Altium Limited"))
      (libsource (lib "BKIT4U_LIB") (part "Resistor"))
    )
    (comp (ref "R50")
      (value "4K7")
      (footprint "R 0805 (2012)")
      (description "Resistor")
      (fields (field (name "PUBLISHER") "Altium Limited"))
      (libsource (lib "BKIT4U_LIB") (part "Resistor"))
    )
    (comp (ref "R51")
      (value "10K")
      (footprint "R 0805 (2012)")
      (description "Resistor")
      (fields (field (name "PUBLISHER") "Altium Limited"))
      (libsource (lib "BKIT4U_LIB") (part "Resistor"))
    )
    (comp (ref "R52")
      (value "100K")
      (footprint "R 0805 (2012)")
      (description "Resistor")
      (fields (field (name "PUBLISHER") "Altium Limited"))
      (libsource (lib "BKIT4U_LIB") (part "Resistor"))
    )
    (comp (ref "RL1")
      (value "Relay 10A/12V")
      (footprint "RL_SPDT_10A")
      (description "Relay SPDT,10A - 12VDC 5 Pin")
      (libsource (lib "BKIT4U_LIB") (part "Relay 1"))
    )
    (comp (ref "RL2")
      (value "Relay 10A/12V")
      (footprint "RL_SPDT_10A")
      (description "Relay SPDT,10A - 12VDC 5 Pin")
      (libsource (lib "BKIT4U_LIB") (part "Relay 1"))
    )
    (comp (ref "RL3")
      (value "Relay 10A/12V")
      (footprint "RL_SPDT_10A")
      (description "Relay SPDT,10A - 12VDC 5 Pin")
      (libsource (lib "BKIT4U_LIB") (part "Relay 1"))
    )
    (comp (ref "RL4")
      (value "Relay 10A/12V")
      (footprint "RL_SPDT_10A")
      (description "Relay SPDT,10A - 12VDC 5 Pin")
      (libsource (lib "BKIT4U_LIB") (part "Relay 1"))
    )
    (comp (ref "RL5")
      (value "Relay 10A/12V")
      (footprint "RL_SPDT_10A")
      (description "Relay SPDT,10A - 12VDC 5 Pin")
      (libsource (lib "BKIT4U_LIB") (part "Relay 1"))
    )
    (comp (ref "RL6")
      (value "Relay 10A/12V")
      (footprint "RL_SPDT_10A")
      (description "Relay SPDT,10A - 12VDC 5 Pin")
      (libsource (lib "BKIT4U_LIB") (part "Relay 1"))
    )
    (comp (ref "SW1")
      (value "SW DIP-5")
      (footprint "SW/DIP5/300")
      (libsource (lib "chipfc_altium_libs") (part "SW DIP-5"))
    )
    (comp (ref "SW2")
      (value "Button")
      (footprint "SW/2/SMD")
      (description "Tact switch 2 pin")
      (libsource (lib "BKIT4U_LIB") (part "SW SPST"))
    )
    (comp (ref "U2")
      (value "7805")
      (footprint "TO-252 (DPAK)")
      (description "LDO Fixed Voltage regulator")
      (libsource (lib "BKIT4U_LIB") (part "78xx"))
    )
    (comp (ref "U3")
      (value "PC817")
      (footprint "SOP4 - PC817")
      (description "Single Opto")
      (libsource (lib "syhaunguyen") (part "PC817"))
    )
    (comp (ref "U4") (value "ACS712") (footprint "SO-8 HCPL") (libsource (lib "ACS712") (part "ACS712")))
    (comp (ref "U5") (value "SN75176BDR") (footprint "SOIC-8") (libsource (lib "BKIT4U_LIB") (part "MAX485")))
    (comp (ref "U6")
      (value "PC817")
      (footprint "SOP4 - PC817")
      (description "Single Opto")
      (libsource (lib "syhaunguyen") (part "PC817"))
    )
    (comp (ref "U7")
      (value "PC817")
      (footprint "SOP4 - PC817")
      (description "Single Opto")
      (libsource (lib "syhaunguyen") (part "PC817"))
    )
    (comp (ref "U8")
      (value "ATmega328-AU")
      (footprint "QFP32N")
      (fields (field (name "PUBLISHER") "Altium Limited"))
      (libsource (lib "Atmel Microcontroller 8-Bit megaAVR") (part "ATmega328-AU"))
    )
    (comp (ref "U9")
      (value "PC817")
      (footprint "SOP4 - PC817")
      (description "Single Opto")
      (libsource (lib "syhaunguyen") (part "PC817"))
    )
    (comp (ref "U10") (value "ACS712") (footprint "SO-8 HCPL") (libsource (lib "ACS712") (part "ACS712")))
    (comp (ref "U11")
      (value "74HC245D")
      (footprint "SOIC-20")
      (description "IC TRANSCVR NON-INVERT 6V 20SO")
      (libsource (lib "chipfc_altium_libs") (part "74HC245D"))
    )
    (comp (ref "U12")
      (value "PC817")
      (footprint "SOP4 - PC817")
      (description "Single Opto")
      (libsource (lib "syhaunguyen") (part "PC817"))
    )
    (comp (ref "U13")
      (value "PC817")
      (footprint "SOP4 - PC817")
      (description "Single Opto")
      (libsource (lib "syhaunguyen") (part "PC817"))
    )
    (comp (ref "U14")
      (value "PC817")
      (footprint "SOP4 - PC817")
      (description "Single Opto")
      (libsource (lib "syhaunguyen") (part "PC817"))
    )
    (comp (ref "U15") (value "ACS712") (footprint "SO-8 HCPL") (libsource (lib "ACS712") (part "ACS712")))
    (comp (ref "U16")
      (value "PC817")
      (footprint "SOP4 - PC817")
      (description "Single Opto")
      (libsource (lib "syhaunguyen") (part "PC817"))
    )
    (comp (ref "U17")
      (value "PC817")
      (footprint "SOP4 - PC817")
      (description "Single Opto")
      (libsource (lib "syhaunguyen") (part "PC817"))
    )
    (comp (ref "U301")
      (value "7809")
      (footprint "TO-252 (DPAK)")
      (description "LDO Fixed Voltage regulator")
      (libsource (lib "BKIT4U_LIB") (part "78xx"))
    )
    (comp (ref "VR1")
      (value "Varistor")
      (footprint "VARISTOR DISC 5MM/7MM")
      (libsource (lib "chipfc_altium_libs") (part "Varistor"))
    )
    (comp (ref "Y1")
      (value "16MHz")
      (footprint "XTAL")
      (description "Crystal Oscillator")
      (fields (field (name "PUBLISHER") "Altium Limited"))
      (libsource (lib "phong") (part "XTAL"))
    )
    (comp (ref "Y2")
      (value "~")
      (footprint "Crystal SMD CSTCE")
      (libsource (lib "BKIT4U_LIB") (part "Crystal CSTCE"))
    )
  )
  (nets
    (net (code "1") (name "/A") (class "Default")
      (node (ref "D6") (pin "2") (pinfunction "K_2") (pintype "passive"))
      (node (ref "P3") (pin "1") (pinfunction "1_1") (pintype "passive"))
      (node (ref "P301") (pin "1") (pinfunction "1_1") (pintype "passive"))
      (node (ref "R12") (pin "2") (pinfunction "2_2") (pintype "passive"))
      (node (ref "R9") (pin "1") (pinfunction "1_1") (pintype "passive"))
      (node (ref "U5") (pin "6") (pinfunction "A_6") (pintype "passive"))
    )
    (net (code "2") (name "/AREF") (class "Default")
      (node (ref "C22") (pin "2") (pinfunction "2_2") (pintype "passive"))
      (node (ref "U8") (pin "20") (pinfunction "AREF_20") (pintype "passive"))
    )
    (net (code "3") (name "/B") (class "Default")
      (node (ref "D8") (pin "2") (pinfunction "K_2") (pintype "passive"))
      (node (ref "P3") (pin "2") (pinfunction "2_2") (pintype "passive"))
      (node (ref "P301") (pin "2") (pinfunction "2_2") (pintype "passive"))
      (node (ref "R12") (pin "1") (pinfunction "1_1") (pintype "passive"))
      (node (ref "R15") (pin "2") (pinfunction "2_2") (pintype "passive"))
      (node (ref "U5") (pin "7") (pinfunction "B_7") (pintype "passive"))
    )
    (net (code "4") (name "/DEBUG_LED") (class "Default")
      (node (ref "CN1") (pin "3") (pinfunction "3_3") (pintype "passive"))
      (node (ref "R38") (pin "1") (pinfunction "1_1") (pintype "passive"))
      (node (ref "U8") (pin "17") (pinfunction "PB5_(SCK/PCINT5)_17") (pintype "bidirectional"))
    )
    (net (code "5") (name "/DI") (class "Default")
      (node (ref "P5") (pin "2") (pinfunction "2_2") (pintype "passive"))
      (node (ref "R14") (pin "1") (pinfunction "1_1") (pintype "passive"))
      (node (ref "U5") (pin "4") (pinfunction "DI_4") (pintype "input"))
      (node (ref "U8") (pin "31") (pinfunction "PD1_(TXD/PCINT17)_31") (pintype "bidirectional"))
    )
    (net (code "6") (name "/EN") (class "Default")
      (node (ref "R11") (pin "1") (pinfunction "1_1") (pintype "passive"))
      (node (ref "U5") (pin "2") (pinfunction "~{RE}_2") (pintype "input"))
      (node (ref "U5") (pin "3") (pinfunction "DE_3") (pintype "input"))
      (node (ref "U8") (pin "32") (pinfunction "PD2_(INT0/PCINT18)_32") (pintype "bidirectional"))
    )
    (net (code "7") (name "/M1") (class "Default")
      (node (ref "Q3") (pin "2") (pinfunction "D_2") (pintype "passive"))
      (node (ref "RL1") (pin "3") (pinfunction "3_3") (pintype "passive"))
      (node (ref "RL2") (pin "3") (pinfunction "3_3") (pintype "passive"))
    )
    (net (code "8") (name "/M1_PWM") (class "Default")
      (node (ref "R18") (pin "2") (pinfunction "2_2") (pintype "passive"))
      (node (ref "U8") (pin "9") (pinfunction "PD5_(PCINT21/OC0B/T1)_9") (pintype "bidirectional"))
    )
    (net (code "9") (name "/M2") (class "Default")
      (node (ref "Q7") (pin "2") (pinfunction "D_2") (pintype "passive"))
      (node (ref "RL3") (pin "3") (pinfunction "3_3") (pintype "passive"))
      (node (ref "RL4") (pin "3") (pinfunction "3_3") (pintype "passive"))
    )
    (net (code "10") (name "/M2_PWM") (class "Default")
      (node (ref "R41") (pin "2") (pinfunction "2_2") (pintype "passive"))
      (node (ref "U8") (pin "10") (pinfunction "PD6_(PCINT22/OC0A/AIN0)_10") (pintype "bidirectional"))
    )
    (net (code "11") (name "/M3") (class "Default")
      (node (ref "Q11") (pin "2") (pinfunction "D_2") (pintype "passive"))
      (node (ref "RL5") (pin "3") (pinfunction "3_3") (pintype "passive"))
      (node (ref "RL6") (pin "3") (pinfunction "3_3") (pintype "passive"))
    )
    (net (code "12") (name "/M3_PWM") (class "Default")
      (node (ref "R50") (pin "2") (pinfunction "2_2") (pintype "passive"))
      (node (ref "U8") (pin "13") (pinfunction "PB1_(PCINT1/OC1A)_13") (pintype "bidirectional"))
    )
    (net (code "13") (name "/MISO") (class "Default")
      (node (ref "CN1") (pin "1") (pinfunction "1_1") (pintype "passive"))
      (node (ref "R27") (pin "1") (pinfunction "1_1") (pintype "passive"))
      (node (ref "U8") (pin "16") (pinfunction "PB4_(PCINT4/MISO)_16") (pintype "bidirectional"))
    )
    (net (code "14") (name "/MOSI") (class "Default")
      (node (ref "CN1") (pin "4") (pinfunction "4_4") (pintype "passive"))
      (node (ref "R30") (pin "1") (pinfunction "1_1") (pintype "passive"))
      (node (ref "U8") (pin "15") (pinfunction "PB3_(PCINT3/OC2A/MOSI)_15") (pintype "bidirectional"))
    )
    (net (code "15") (name "/O1_M1") (class "Default")
      (node (ref "R31") (pin "1") (pinfunction "1_1") (pintype "passive"))
      (node (ref "U8") (pin "14") (pinfunction "PB2_(PCINT2/~{SS}/OC1B)_14") (pintype "bidirectional"))
    )
    (net (code "16") (name "/O1_M2") (class "Default")
      (node (ref "R35") (pin "1") (pinfunction "1_1") (pintype "passive"))
      (node (ref "U8") (pin "11") (pinfunction "PD7_(PCINT23/AIN1)_11") (pintype "bidirectional"))
    )
    (net (code "17") (name "/O1_M3") (class "Default")
      (node (ref "R37") (pin "1") (pinfunction "1_1") (pintype "passive"))
      (node (ref "U8") (pin "1") (pinfunction "PD3_(PCINT19/OC2B/INT1)_1") (pintype "bidirectional"))
    )
    (net (code "18") (name "/O2_M2") (class "Default")
      (node (ref "R33") (pin "1") (pinfunction "1_1") (pintype "passive"))
      (node (ref "U8") (pin "12") (pinfunction "PB0_(PCINT0/CLKO/ICP1)_12") (pintype "bidirectional"))
    )
    (net (code "19") (name "/O2_M3") (class "Default")
      (node (ref "R36") (pin "1") (pinfunction "1_1") (pintype "passive"))
      (node (ref "U8") (pin "2") (pinfunction "PD4_(PCINT20/XCK/T0)_2") (pintype "bidirectional"))
    )
    (net (code "20") (name "/RELAY1_M1") (class "Default")
      (node (ref "R6") (pin "2") (pinfunction "2_2") (pintype "passive"))
      (node (ref "U11") (pin "17") (pinfunction "B1_17") (pintype "passive"))
    )
    (net (code "21") (name "/RELAY1_M2") (class "Default")
      (node (ref "R21") (pin "2") (pinfunction "2_2") (pintype "passive"))
      (node (ref "U11") (pin "15") (pinfunction "B3_15") (pintype "passive"))
    )
    (net (code "22") (name "/RELAY1_M3") (class "Default")
      (node (ref "R44") (pin "2") (pinfunction "2_2") (pintype "passive"))
      (node (ref "U11") (pin "13") (pinfunction "B5_13") (pintype "passive"))
    )
    (net (code "23") (name "/RELAY2_M1") (class "Default")
      (node (ref "R13") (pin "2") (pinfunction "2_2") (pintype "passive"))
      (node (ref "U11") (pin "18") (pinfunction "B0_18") (pintype "passive"))
    )
    (net (code "24") (name "/RELAY2_M2") (class "Default")
      (node (ref "R32") (pin "2") (pinfunction "2_2") (pintype "passive"))
      (node (ref "U11") (pin "16") (pinfunction "B2_16") (pintype "passive"))
    )
    (net (code "25") (name "/RELAY2_M3") (class "Default")
      (node (ref "R47") (pin "2") (pinfunction "2_2") (pintype "passive"))
      (node (ref "U11") (pin "14") (pinfunction "B4_14") (pintype "passive"))
    )
    (net (code "26") (name "/RESET") (class "Default")
      (node (ref "CN1") (pin "5") (pinfunction "5_5") (pintype "passive"))
      (node (ref "R29") (pin "1") (pinfunction "1_1") (pintype "passive"))
      (node (ref "SW2") (pin "1") (pinfunction "1_1") (pintype "passive"))
      (node (ref "U8") (pin "29") (pinfunction "PC6_(~{RESET}/PCINT14)_29") (pintype "bidirectional"))
    )
    (net (code "27") (name "/RO") (class "Default")
      (node (ref "P5") (pin "1") (pinfunction "1_1") (pintype "passive"))
      (node (ref "R10") (pin "1") (pinfunction "1_1") (pintype "passive"))
      (node (ref "U5") (pin "1") (pinfunction "RO_1") (pintype "output"))
      (node (ref "U8") (pin "30") (pinfunction "PD0_(RXD/PCINT16)_30") (pintype "bidirectional"))
    )
    (net (code "28") (name "/SW1") (class "Default")
      (node (ref "R22") (pin "1") (pinfunction "1_1") (pintype "passive"))
      (node (ref "U8") (pin "28") (pinfunction "PC5_(ADC5/SCL/PCINT13)_28") (pintype "bidirectional"))
    )
    (net (code "29") (name "/SW2") (class "Default")
      (node (ref "R23") (pin "1") (pinfunction "1_1") (pintype "passive"))
      (node (ref "U8") (pin "27") (pinfunction "PC4_(ADC4/SDA/PCINT12)_27") (pintype "bidirectional"))
    )
    (net (code "30") (name "/SW3") (class "Default")
      (node (ref "R25") (pin "1") (pinfunction "1_1") (pintype "passive"))
      (node (ref "U8") (pin "26") (pinfunction "PC3_(ADC3/PCINT11)_26") (pintype "bidirectional"))
    )
    (net (code "31") (name "/SW4") (class "Default")
      (node (ref "R26") (pin "1") (pinfunction "1_1") (pintype "passive"))
      (node (ref "U8") (pin "25") (pinfunction "PC2_(ADC2/PCINT10)_25") (pintype "bidirectional"))
    )
    (net (code "32") (name "/TEMP") (class "Default")
      (node (ref "C8") (pin "1") (pinfunction "1_1") (pintype "passive"))
      (node (ref "R2") (pin "2") (pinfunction "2_2") (pintype "passive"))
      (node (ref "U8") (pin "19") (pinfunction "ADC6_19") (pintype "input"))
    )
    (net (code "33") (name "/VOUT_M1") (class "Default")
      (node (ref "C13") (pin "2") (pinfunction "2_2") (pintype "passive"))
      (node (ref "R8") (pin "2") (pinfunction "2_2") (pintype "passive"))
      (node (ref "U8") (pin "23") (pinfunction "PC0_(ADC0/PCINT8)_23") (pintype "bidirectional"))
    )
    (net (code "34") (name "/VOUT_M2") (class "Default")
      (node (ref "C25") (pin "2") (pinfunction "2_2") (pintype "passive"))
      (node (ref "R28") (pin "2") (pinfunction "2_2") (pintype "passive"))
      (node (ref "U8") (pin "24") (pinfunction "PC1_(ADC1/PCINT9)_24") (pintype "bidirectional"))
    )
    (net (code "35") (name "/VOUT_M3") (class "Default")
      (node (ref "C35") (pin "2") (pinfunction "2_2") (pintype "passive"))
      (node (ref "R46") (pin "2") (pinfunction "2_2") (pintype "passive"))
      (node (ref "U8") (pin "22") (pinfunction "ADC7_22") (pintype "input"))
    )
    (net (code "36") (name "/re1") (class "Default")
      (node (ref "C107") (pin "1") (pinfunction "1_1") (pintype "passive"))
      (node (ref "R30") (pin "2") (pinfunction "2_2") (pintype "passive"))
      (node (ref "U11") (pin "2") (pinfunction "A0_2") (pintype "passive"))
    )
    (net (code "37") (name "/re2") (class "Default")
      (node (ref "C106") (pin "1") (pinfunction "1_1") (pintype "passive"))
      (node (ref "R31") (pin "2") (pinfunction "2_2") (pintype "passive"))
      (node (ref "U11") (pin "3") (pinfunction "A1_3") (pintype "passive"))
    )
    (net (code "38") (name "/re3") (class "Default")
      (node (ref "C104") (pin "1") (pinfunction "1_1") (pintype "passive"))
      (node (ref "R33") (pin "2") (pinfunction "2_2") (pintype "passive"))
      (node (ref "U11") (pin "4") (pinfunction "A2_4") (pintype "passive"))
    )
    (net (code "39") (name "/re4") (class "Default")
      (node (ref "C103") (pin "1") (pinfunction "1_1") (pintype "passive"))
      (node (ref "R35") (pin "2") (pinfunction "2_2") (pintype "passive"))
      (node (ref "U11") (pin "5") (pinfunction "A3_5") (pintype "passive"))
    )
    (net (code "40") (name "/re5") (class "Default")
      (node (ref "C102") (pin "1") (pinfunction "1_1") (pintype "passive"))
      (node (ref "R36") (pin "2") (pinfunction "2_2") (pintype "passive"))
      (node (ref "U11") (pin "6") (pinfunction "A4_6") (pintype "passive"))
    )
    (net (code "41") (name "/re6") (class "Default")
      (node (ref "C101") (pin "1") (pinfunction "1_1") (pintype "passive"))
      (node (ref "R37") (pin "2") (pinfunction "2_2") (pintype "passive"))
      (node (ref "U11") (pin "7") (pinfunction "A5_7") (pintype "passive"))
    )
    (net (code "42") (name "5V") (class "Default")
      (node (ref "C12") (pin "2") (pinfunction "2_2") (pintype "passive"))
      (node (ref "C15") (pin "1") (pinfunction "1_1") (pintype "passive"))
      (node (ref "C2") (pin "1") (pinfunction "1_1") (pintype "passive"))
      (node (ref "C24") (pin "2") (pinfunction "2_2") (pintype "passive"))
      (node (ref "C34") (pin "2") (pinfunction "2_2") (pintype "passive"))
      (node (ref "C7") (pin "1") (pinfunction "1_1") (pintype "passive"))
      (node (ref "D2") (pin "2") (pinfunction "K_2") (pintype "passive"))
      (node (ref "D3") (pin "2") (pinfunction "K_2") (pintype "passive"))
      (node (ref "L3") (pin "2") (pinfunction "2_2") (pintype "passive"))
      (node (ref "L4") (pin "2") (pinfunction "2_2") (pintype "passive"))
      (node (ref "R1") (pin "1") (pinfunction "1_1") (pintype "passive"))
      (node (ref "R9") (pin "2") (pinfunction "2_2") (pintype "passive"))
      (node (ref "U10") (pin "8") (pinfunction "VCC_8") (pintype "passive"))
      (node (ref "U11") (pin "1") (pinfunction "DIR_1") (pintype "passive"))
      (node (ref "U11") (pin "20") (pinfunction "VCC_20") (pintype "passive"))
      (node (ref "U12") (pin "1") (pinfunction "A_1") (pintype "passive"))
      (node (ref "U13") (pin "1") (pinfunction "A_1") (pintype "passive"))
      (node (ref "U14") (pin "1") (pinfunction "A_1") (pintype "passive"))
      (node (ref "U15") (pin "8") (pinfunction "VCC_8") (pintype "passive"))
      (node (ref "U16") (pin "1") (pinfunction "A_1") (pintype "passive"))
      (node (ref "U17") (pin "1") (pinfunction "A_1") (pintype "passive"))
      (node (ref "U3") (pin "1") (pinfunction "A_1") (pintype "passive"))
      (node (ref "U4") (pin "8") (pinfunction "VCC_8") (pintype "passive"))
      (node (ref "U5") (pin "8") (pinfunction "VCC_8") (pintype "passive"))
      (node (ref "U6") (pin "1") (pinfunction "A_1") (pintype "passive"))
      (node (ref "U7") (pin "1") (pinfunction "A_1") (pintype "passive"))
      (node (ref "U9") (pin "1") (pinfunction "A_1") (pintype "passive"))
    )
    (net (code "43") (name "12VIN") (class "Default")
      (node (ref "C1") (pin "2") (pinfunction "2_2") (pintype "passive"))
      (node (ref "C11") (pin "1") (pinfunction "1_1") (pintype "passive"))
      (node (ref "C17") (pin "2") (pinfunction "2_2") (pintype "passive"))
      (node (ref "C18") (pin "1") (pinfunction "1_1") (pintype "passive"))
      (node (ref "C181") (pin "1") (pinfunction "1_1") (pintype "passive"))
      (node (ref "C182") (pin "1") (pinfunction "1_1") (pintype "passive"))
      (node (ref "C20") (pin "2") (pinfunction "2_2") (pintype "passive"))
      (node (ref "C28") (pin "2") (pinfunction "2_2") (pintype "passive"))
      (node (ref "C32") (pin "2") (pinfunction "2_2") (pintype "passive"))
      (node (ref "C38") (pin "2") (pinfunction "2_2") (pintype "passive"))
      (node (ref "D10") (pin "2") (pinfunction "K_2") (pintype "passive"))
      (node (ref "D11") (pin "2") (pinfunction "K_2") (pintype "passive"))
      (node (ref "D12") (pin "2") (pinfunction "K_2") (pintype "passive"))
      (node (ref "D4") (pin "2") (pinfunction "K_2") (pintype "passive"))
      (node (ref "D7") (pin "2") (pinfunction "K_2") (pintype "passive"))
      (node (ref "D9") (pin "2") (pinfunction "K_2") (pintype "passive"))
      (node (ref "F1") (pin "1") (pinfunction "1_1") (pintype "passive"))
      (node (ref "P1") (pin "1") (pinfunction "1_1") (pintype "passive"))
      (node (ref "RL1") (pin "2") (pinfunction "2_2") (pintype "passive"))
      (node (ref "RL1") (pin "5") (pinfunction "5_5") (pintype "passive"))
      (node (ref "RL2") (pin "2") (pinfunction "2_2") (pintype "passive"))
      (node (ref "RL2") (pin "5") (pinfunction "5_5") (pintype "passive"))
      (node (ref "RL3") (pin "2") (pinfunction "2_2") (pintype "passive"))
      (node (ref "RL3") (pin "5") (pinfunction "5_5") (pintype "passive"))
      (node (ref "RL4") (pin "2") (pinfunction "2_2") (pintype "passive"))
      (node (ref "RL4") (pin "5") (pinfunction "5_5") (pintype "passive"))
      (node (ref "RL5") (pin "2") (pinfunction "2_2") (pintype "passive"))
      (node (ref "RL5") (pin "5") (pinfunction "5_5") (pintype "passive"))
      (node (ref "RL6") (pin "2") (pinfunction "2_2") (pintype "passive"))
      (node (ref "RL6") (pin "5") (pinfunction "5_5") (pintype "passive"))
      (node (ref "U12") (pin "4") (pinfunction "C_4") (pintype "passive"))
      (node (ref "U13") (pin "4") (pinfunction "C_4") (pintype "passive"))
      (node (ref "U14") (pin "4") (pinfunction "C_4") (pintype "passive"))
      (node (ref "U16") (pin "4") (pinfunction "C_4") (pintype "passive"))
      (node (ref "U17") (pin "4") (pinfunction "C_4") (pintype "passive"))
      (node (ref "U3") (pin "4") (pinfunction "C_4") (pintype "passive"))
      (node (ref "U6") (pin "4") (pinfunction "C_4") (pintype "passive"))
      (node (ref "U7") (pin "4") (pinfunction "C_4") (pintype "passive"))
      (node (ref "U9") (pin "4") (pinfunction "C_4") (pintype "passive"))
    )
    (net (code "44") (name "GND") (class "Default")
      (node (ref "C10") (pin "2") (pinfunction "2_2") (pintype "passive"))
      (node (ref "C101") (pin "2") (pinfunction "2_2") (pintype "passive"))
      (node (ref "C102") (pin "2") (pinfunction "2_2") (pintype "passive"))
      (node (ref "C103") (pin "2") (pinfunction "2_2") (pintype "passive"))
      (node (ref "C104") (pin "2") (pinfunction "2_2") (pintype "passive"))
      (node (ref "C106") (pin "2") (pinfunction "2_2") (pintype "passive"))
      (node (ref "C107") (pin "2") (pinfunction "2_2") (pintype "passive"))
      (node (ref "C12") (pin "1") (pinfunction "1_1") (pintype "passive"))
      (node (ref "C13") (pin "1") (pinfunction "1_1") (pintype "passive"))
      (node (ref "C15") (pin "2") (pinfunction "2_2") (pintype "passive"))
      (node (ref "C16") (pin "1") (pinfunction "1_1") (pintype "passive"))
      (node (ref "C19") (pin "2") (pinfunction "2_2") (pintype "passive"))
      (node (ref "C2") (pin "2") (pinfunction "2_2") (pintype "passive"))
      (node (ref "C201") (pin "2") (pinfunction "2_2") (pintype "passive"))
      (node (ref "C202") (pin "2") (pinfunction "2_2") (pintype "passive"))
      (node (ref "C21") (pin "1") (pinfunction "1_1") (pintype "passive"))
      (node (ref "C22") (pin "1") (pinfunction "1_1") (pintype "passive"))
      (node (ref "C24") (pin "1") (pinfunction "1_1") (pintype "passive"))
      (node (ref "C25") (pin "1") (pinfunction "1_1") (pintype "passive"))
      (node (ref "C27") (pin "1") (pinfunction "1_1") (pintype "passive"))
      (node (ref "C3") (pin "2") (pinfunction "2_2") (pintype "passive"))
      (node (ref "C30") (pin "1") (pinfunction "1_1") (pintype "passive"))
      (node (ref "C31") (pin "1") (pinfunction "1_1") (pintype "passive"))
      (node (ref "C34") (pin "1") (pinfunction "1_1") (pintype "passive"))
      (node (ref "C35") (pin "1") (pinfunction "1_1") (pintype "passive"))
      (node (ref "C37") (pin "1") (pinfunction "1_1") (pintype "passive"))
      (node (ref "C4") (pin "2") (pinfunction "2_2") (pintype "passive"))
      (node (ref "C5") (pin "2") (pinfunction "2_2") (pintype "passive"))
      (node (ref "C6") (pin "2") (pinfunction "2_2") (pintype "passive"))
      (node (ref "C7") (pin "2") (pinfunction "2_2") (pintype "passive"))
      (node (ref "C8") (pin "2") (pinfunction "2_2") (pintype "passive"))
      (node (ref "C9") (pin "2") (pinfunction "2_2") (pintype "passive"))
      (node (ref "CN1") (pin "6") (pinfunction "6_6") (pintype "passive"))
      (node (ref "D1") (pin "1") (pinfunction "A_1") (pintype "passive"))
      (node (ref "D2") (pin "1") (pinfunction "A_1") (pintype "passive"))
      (node (ref "D3") (pin "1") (pinfunction "A_1") (pintype "passive"))
      (node (ref "D6") (pin "1") (pinfunction "A_1") (pintype "passive"))
      (node (ref "D8") (pin "1") (pinfunction "A_1") (pintype "passive"))
      (node (ref "L201") (pin "2") (pinfunction "2_2") (pintype "passive"))
      (node (ref "LED1") (pin "2") (pinfunction "K_2") (pintype "passive"))
      (node (ref "P101") (pin "1") (pinfunction "1_1") (pintype "passive"))
      (node (ref "P5") (pin "4") (pinfunction "4_4") (pintype "passive"))
      (node (ref "Q12") (pin "2") (pinfunction "E_2") (pintype "passive"))
      (node (ref "Q4") (pin "2") (pinfunction "E_2") (pintype "passive"))
      (node (ref "Q8") (pin "2") (pinfunction "E_2") (pintype "passive"))
      (node (ref "R15") (pin "1") (pinfunction "1_1") (pintype "passive"))
      (node (ref "R20") (pin "1") (pinfunction "1_1") (pintype "passive"))
      (node (ref "R4") (pin "2") (pinfunction "2_2") (pintype "passive"))
      (node (ref "R43") (pin "1") (pinfunction "1_1") (pintype "passive"))
      (node (ref "R52") (pin "1") (pinfunction "1_1") (pintype "passive"))
      (node (ref "SW1") (pin "10") (pinfunction "10_10") (pintype "passive"))
      (node (ref "SW1") (pin "6") (pinfunction "6_6") (pintype "passive"))
      (node (ref "SW1") (pin "7") (pinfunction "7_7") (pintype "passive"))
      (node (ref "SW1") (pin "8") (pinfunction "8_8") (pintype "passive"))
      (node (ref "SW1") (pin "9") (pinfunction "9_9") (pintype "passive"))
      (node (ref "SW2") (pin "2") (pinfunction "2_2") (pintype "passive"))
      (node (ref "U10") (pin "5") (pinfunction "GND_5") (pintype "passive"))
      (node (ref "U11") (pin "10") (pinfunction "GND_10") (pintype "passive"))
      (node (ref "U11") (pin "19") (pinfunction "~{OE}_19") (pintype "passive"))
      (node (ref "U15") (pin "5") (pinfunction "GND_5") (pintype "passive"))
      (node (ref "U2") (pin "2") (pinfunction "GND_2") (pintype "passive"))
      (node (ref "U301") (pin "2") (pinfunction "GND_2") (pintype "passive"))
      (node (ref "U4") (pin "5") (pinfunction "GND_5") (pintype "passive"))
      (node (ref "U5") (pin "5") (pinfunction "GND_5") (pintype "power_in"))
      (node (ref "U8") (pin "21") (pinfunction "GND_21") (pintype "power_in"))
      (node (ref "U8") (pin "3") (pinfunction "GND_3") (pintype "power_in"))
      (node (ref "U8") (pin "5") (pinfunction "GND_5") (pintype "power_in"))
      (node (ref "Y2") (pin "2") (pinfunction "2_2") (pintype "passive"))
    )
    (net (code "45") (name "GND_IN") (class "Default")
      (node (ref "C11") (pin "2") (pinfunction "2_2") (pintype "passive"))
      (node (ref "C18") (pin "2") (pinfunction "2_2") (pintype "passive"))
      (node (ref "C181") (pin "2") (pinfunction "2_2") (pintype "passive"))
      (node (ref "C182") (pin "2") (pinfunction "2_2") (pintype "passive"))
      (node (ref "L201") (pin "1") (pinfunction "1_1") (pintype "passive"))
      (node (ref "Q1") (pin "1") (pinfunction "E_1") (pintype "passive"))
      (node (ref "Q10") (pin "1") (pinfunction "E_1") (pintype "passive"))
      (node (ref "Q11") (pin "3") (pinfunction "S_3") (pintype "passive"))
      (node (ref "Q2") (pin "1") (pinfunction "E_1") (pintype "passive"))
      (node (ref "Q3") (pin "3") (pinfunction "S_3") (pintype "passive"))
      (node (ref "Q5") (pin "1") (pinfunction "E_1") (pintype "passive"))
      (node (ref "Q6") (pin "1") (pinfunction "E_1") (pintype "passive"))
      (node (ref "Q7") (pin "3") (pinfunction "S_3") (pintype "passive"))
      (node (ref "Q9") (pin "1") (pinfunction "E_1") (pintype "passive"))
      (node (ref "R19") (pin "1") (pinfunction "1_1") (pintype "passive"))
      (node (ref "R42") (pin "2") (pinfunction "2_2") (pintype "passive"))
      (node (ref "R51") (pin "2") (pinfunction "2_2") (pintype "passive"))
      (node (ref "VR1") (pin "2") (pinfunction "2_2") (pintype "passive"))
    )
    (net (code "46") (name "Net-(C14-Pad1)") (class "Default")
      (node (ref "C14") (pin "1") (pinfunction "1_1") (pintype "passive"))
      (node (ref "P2") (pin "1") (pinfunction "1_1") (pintype "passive"))
      (node (ref "RL2") (pin "1") (pinfunction "1_1") (pintype "passive"))
    )
    (net (code "47") (name "Net-(C14-Pad2)") (class "Default")
      (node (ref "C14") (pin "2") (pinfunction "2_2") (pintype "passive"))
      (node (ref "F2") (pin "1") (pinfunction "1_1") (pintype "passive"))
      (node (ref "P2") (pin "2") (pinfunction "2_2") (pintype "passive"))
    )
    (net (code "48") (name "Net-(C26-Pad1)") (class "Default")
      (node (ref "C26") (pin "1") (pinfunction "1_1") (pintype "passive"))
      (node (ref "P4") (pin "1") (pinfunction "1_1") (pintype "passive"))
      (node (ref "RL4") (pin "1") (pinfunction "1_1") (pintype "passive"))
    )
    (net (code "49") (name "Net-(C26-Pad2)") (class "Default")
      (node (ref "C26") (pin "2") (pinfunction "2_2") (pintype "passive"))
      (node (ref "F3") (pin "1") (pinfunction "1_1") (pintype "passive"))
      (node (ref "P4") (pin "2") (pinfunction "2_2") (pintype "passive"))
    )
    (net (code "50") (name "Net-(C36-Pad1)") (class "Default")
      (node (ref "C36") (pin "1") (pinfunction "1_1") (pintype "passive"))
      (node (ref "P6") (pin "1") (pinfunction "1_1") (pintype "passive"))
      (node (ref "RL6") (pin "1") (pinfunction "1_1") (pintype "passive"))
    )
    (net (code "51") (name "Net-(C36-Pad2)") (class "Default")
      (node (ref "C36") (pin "2") (pinfunction "2_2") (pintype "passive"))
      (node (ref "F4") (pin "1") (pinfunction "1_1") (pintype "passive"))
      (node (ref "P6") (pin "2") (pinfunction "2_2") (pintype "passive"))
    )
    (net (code "52") (name "Net-(D1-K)") (class "Default")
      (node (ref "D1") (pin "2") (pinfunction "K_2") (pintype "passive"))
      (node (ref "F1") (pin "2") (pinfunction "2_2") (pintype "passive"))
      (node (ref "L1") (pin "1") (pinfunction "1_1") (pintype "passive"))
      (node (ref "VR1") (pin "1") (pinfunction "1_1") (pintype "passive"))
    )
    (net (code "53") (name "Net-(D4-A)") (class "Default")
      (node (ref "C1") (pin "1") (pinfunction "1_1") (pintype "passive"))
      (node (ref "D4") (pin "1") (pinfunction "A_1") (pintype "passive"))
      (node (ref "Q1") (pin "2") (pinfunction "C_2") (pintype "passive"))
      (node (ref "RL1") (pin "4") (pinfunction "4_4") (pintype "passive"))
    )
    (net (code "54") (name "Net-(D7-A)") (class "Default")
      (node (ref "C17") (pin "1") (pinfunction "1_1") (pintype "passive"))
      (node (ref "D7") (pin "1") (pinfunction "A_1") (pintype "passive"))
      (node (ref "Q2") (pin "2") (pinfunction "C_2") (pintype "passive"))
      (node (ref "RL2") (pin "4") (pinfunction "4_4") (pintype "passive"))
    )
    (net (code "55") (name "Net-(D9-A)") (class "Default")
      (node (ref "C20") (pin "1") (pinfunction "1_1") (pintype "passive"))
      (node (ref "D9") (pin "1") (pinfunction "A_1") (pintype "passive"))
      (node (ref "Q5") (pin "2") (pinfunction "C_2") (pintype "passive"))
      (node (ref "RL3") (pin "4") (pinfunction "4_4") (pintype "passive"))
    )
    (net (code "56") (name "Net-(D10-A)") (class "Default")
      (node (ref "C28") (pin "1") (pinfunction "1_1") (pintype "passive"))
      (node (ref "D10") (pin "1") (pinfunction "A_1") (pintype "passive"))
      (node (ref "Q6") (pin "2") (pinfunction "C_2") (pintype "passive"))
      (node (ref "RL4") (pin "4") (pinfunction "4_4") (pintype "passive"))
    )
    (net (code "57") (name "Net-(D11-A)") (class "Default")
      (node (ref "C32") (pin "1") (pinfunction "1_1") (pintype "passive"))
      (node (ref "D11") (pin "1") (pinfunction "A_1") (pintype "passive"))
      (node (ref "Q9") (pin "2") (pinfunction "C_2") (pintype "passive"))
      (node (ref "RL5") (pin "4") (pinfunction "4_4") (pintype "passive"))
    )
    (net (code "58") (name "Net-(D12-A)") (class "Default")
      (node (ref "C38") (pin "1") (pinfunction "1_1") (pintype "passive"))
      (node (ref "D12") (pin "1") (pinfunction "A_1") (pintype "passive"))
      (node (ref "Q10") (pin "2") (pinfunction "C_2") (pintype "passive"))
      (node (ref "RL6") (pin "4") (pinfunction "4_4") (pintype "passive"))
    )
    (net (code "59") (name "Net-(F2-Pad2)") (class "Default")
      (node (ref "F2") (pin "2") (pinfunction "2_2") (pintype "passive"))
      (node (ref "U4") (pin "1") (pinfunction "IP+_1") (pintype "passive"))
      (node (ref "U4") (pin "2") (pinfunction "IP+_2") (pintype "passive"))
    )
    (net (code "60") (name "Net-(F3-Pad2)") (class "Default")
      (node (ref "F3") (pin "2") (pinfunction "2_2") (pintype "passive"))
      (node (ref "U10") (pin "1") (pinfunction "IP+_1") (pintype "passive"))
      (node (ref "U10") (pin "2") (pinfunction "IP+_2") (pintype "passive"))
    )
    (net (code "61") (name "Net-(F4-Pad2)") (class "Default")
      (node (ref "F4") (pin "2") (pinfunction "2_2") (pintype "passive"))
      (node (ref "U15") (pin "1") (pinfunction "IP+_1") (pintype "passive"))
      (node (ref "U15") (pin "2") (pinfunction "IP+_2") (pintype "passive"))
    )
    (net (code "62") (name "Net-(LED1-A)") (class "Default")
      (node (ref "LED1") (pin "1") (pinfunction "A_1") (pintype "passive"))
      (node (ref "R39") (pin "2") (pinfunction "2_2") (pintype "passive"))
    )
    (net (code "63") (name "Net-(Q1-B)") (class "Default")
      (node (ref "Q1") (pin "3") (pinfunction "B_3") (pintype "passive"))
      (node (ref "R7") (pin "2") (pinfunction "2_2") (pintype "passive"))
    )
    (net (code "64") (name "Net-(Q2-B)") (class "Default")
      (node (ref "Q2") (pin "3") (pinfunction "B_3") (pintype "passive"))
      (node (ref "R16") (pin "2") (pinfunction "2_2") (pintype "passive"))
    )
    (net (code "65") (name "Net-(Q3-G)") (class "Default")
      (node (ref "Q3") (pin "1") (pinfunction "G_1") (pintype "passive"))
      (node (ref "R19") (pin "2") (pinfunction "2_2") (pintype "passive"))
      (node (ref "U7") (pin "3") (pinfunction "E_3") (pintype "passive"))
    )
    (net (code "66") (name "Net-(Q4-B)") (class "Default")
      (node (ref "Q4") (pin "1") (pinfunction "B_1") (pintype "passive"))
      (node (ref "R18") (pin "1") (pinfunction "1_1") (pintype "passive"))
      (node (ref "R20") (pin "2") (pinfunction "2_2") (pintype "passive"))
    )
    (net (code "67") (name "Net-(Q4-C)") (class "Default")
      (node (ref "Q4") (pin "3") (pinfunction "C_3") (pintype "passive"))
      (node (ref "R17") (pin "1") (pinfunction "1_1") (pintype "passive"))
    )
    (net (code "68") (name "Net-(Q5-B)") (class "Default")
      (node (ref "Q5") (pin "3") (pinfunction "B_3") (pintype "passive"))
      (node (ref "R24") (pin "2") (pinfunction "2_2") (pintype "passive"))
    )
    (net (code "69") (name "Net-(Q6-B)") (class "Default")
      (node (ref "Q6") (pin "3") (pinfunction "B_3") (pintype "passive"))
      (node (ref "R34") (pin "2") (pinfunction "2_2") (pintype "passive"))
    )
    (net (code "70") (name "Net-(Q7-G)") (class "Default")
      (node (ref "Q7") (pin "1") (pinfunction "G_1") (pintype "passive"))
      (node (ref "R42") (pin "1") (pinfunction "1_1") (pintype "passive"))
      (node (ref "U13") (pin "3") (pinfunction "E_3") (pintype "passive"))
    )
    (net (code "71") (name "Net-(Q8-B)") (class "Default")
      (node (ref "Q8") (pin "1") (pinfunction "B_1") (pintype "passive"))
      (node (ref "R41") (pin "1") (pinfunction "1_1") (pintype "passive"))
      (node (ref "R43") (pin "2") (pinfunction "2_2") (pintype "passive"))
    )
    (net (code "72") (name "Net-(Q8-C)") (class "Default")
      (node (ref "Q8") (pin "3") (pinfunction "C_3") (pintype "passive"))
      (node (ref "R40") (pin "1") (pinfunction "1_1") (pintype "passive"))
    )
    (net (code "73") (name "Net-(Q9-B)") (class "Default")
      (node (ref "Q9") (pin "3") (pinfunction "B_3") (pintype "passive"))
      (node (ref "R45") (pin "2") (pinfunction "2_2") (pintype "passive"))
    )
    (net (code "74") (name "Net-(Q10-B)") (class "Default")
      (node (ref "Q10") (pin "3") (pinfunction "B_3") (pintype "passive"))
      (node (ref "R48") (pin "2") (pinfunction "2_2") (pintype "passive"))
    )
    (net (code "75") (name "Net-(Q11-G)") (class "Default")
      (node (ref "Q11") (pin "1") (pinfunction "G_1") (pintype "passive"))
      (node (ref "R51") (pin "1") (pinfunction "1_1") (pintype "passive"))
      (node (ref "U17") (pin "3") (pinfunction "E_3") (pintype "passive"))
    )
    (net (code "76") (name "Net-(Q12-B)") (class "Default")
      (node (ref "Q12") (pin "1") (pinfunction "B_1") (pintype "passive"))
      (node (ref "R50") (pin "1") (pinfunction "1_1") (pintype "passive"))
      (node (ref "R52") (pin "2") (pinfunction "2_2") (pintype "passive"))
    )
    (net (code "77") (name "Net-(Q12-C)") (class "Default")
      (node (ref "Q12") (pin "3") (pinfunction "C_3") (pintype "passive"))
      (node (ref "R49") (pin "1") (pinfunction "1_1") (pintype "passive"))
    )
    (net (code "78") (name "Net-(R1-Pad2)") (class "Default")
      (node (ref "R1") (pin "2") (pinfunction "2_2") (pintype "passive"))
      (node (ref "R2") (pin "1") (pinfunction "1_1") (pintype "passive"))
      (node (ref "R4") (pin "1") (pinfunction "1_1") (pintype "passive"))
    )
    (net (code "79") (name "Net-(R22-Pad2)") (class "Default")
      (node (ref "R22") (pin "2") (pinfunction "2_2") (pintype "passive"))
      (node (ref "SW1") (pin "1") (pinfunction "1_1") (pintype "passive"))
    )
    (net (code "80") (name "Net-(R23-Pad2)") (class "Default")
      (node (ref "R23") (pin "2") (pinfunction "2_2") (pintype "passive"))
      (node (ref "SW1") (pin "2") (pinfunction "2_2") (pintype "passive"))
    )
    (net (code "81") (name "Net-(R25-Pad2)") (class "Default")
      (node (ref "R25") (pin "2") (pinfunction "2_2") (pintype "passive"))
      (node (ref "SW1") (pin "3") (pinfunction "3_3") (pintype "passive"))
    )
    (net (code "82") (name "Net-(R26-Pad2)") (class "Default")
      (node (ref "R26") (pin "2") (pinfunction "2_2") (pintype "passive"))
      (node (ref "SW1") (pin "4") (pinfunction "4_4") (pintype "passive"))
    )
    (net (code "83") (name "Net-(R27-Pad2)") (class "Default")
      (node (ref "R27") (pin "2") (pinfunction "2_2") (pintype "passive"))
      (node (ref "SW1") (pin "5") (pinfunction "5_5") (pintype "passive"))
    )
    (net (code "84") (name "Net-(RL1-Pad1)") (class "Default")
      (node (ref "RL1") (pin "1") (pinfunction "1_1") (pintype "passive"))
      (node (ref "U4") (pin "3") (pinfunction "IP-_3") (pintype "passive"))
      (node (ref "U4") (pin "4") (pinfunction "IP-_4") (pintype "passive"))
    )
    (net (code "85") (name "Net-(RL3-Pad1)") (class "Default")
      (node (ref "RL3") (pin "1") (pinfunction "1_1") (pintype "passive"))
      (node (ref "U10") (pin "3") (pinfunction "IP-_3") (pintype "passive"))
      (node (ref "U10") (pin "4") (pinfunction "IP-_4") (pintype "passive"))
    )
    (net (code "86") (name "Net-(RL5-Pad1)") (class "Default")
      (node (ref "RL5") (pin "1") (pinfunction "1_1") (pintype "passive"))
      (node (ref "U15") (pin "3") (pinfunction "IP-_3") (pintype "passive"))
      (node (ref "U15") (pin "4") (pinfunction "IP-_4") (pintype "passive"))
    )
    (net (code "87") (name "Net-(U2-Vin)") (class "Default")
      (node (ref "C10") (pin "1") (pinfunction "1_1") (pintype "passive"))
      (node (ref "C6") (pin "1") (pinfunction "1_1") (pintype "passive"))
      (node (ref "L301") (pin "2") (pinfunction "2_2") (pintype "passive"))
      (node (ref "U2") (pin "1") (pinfunction "Vin_1") (pintype "power_in"))
    )
    (net (code "88") (name "Net-(U2-Vout)") (class "Default")
      (node (ref "L3") (pin "1") (pinfunction "1_1") (pintype "passive"))
      (node (ref "U2") (pin "3") (pinfunction "Vout_3") (pintype "passive"))
    )
    (net (code "89") (name "Net-(U3-E)") (class "Default")
      (node (ref "R7") (pin "1") (pinfunction "1_1") (pintype "passive"))
      (node (ref "U3") (pin "3") (pinfunction "E_3") (pintype "passive"))
    )
    (net (code "90") (name "Net-(U3-K)") (class "Default")
      (node (ref "R6") (pin "1") (pinfunction "1_1") (pintype "passive"))
      (node (ref "U3") (pin "2") (pinfunction "K_2") (pintype "passive"))
    )
    (net (code "91") (name "Net-(U4-FILTER)") (class "Default")
      (node (ref "C16") (pin "2") (pinfunction "2_2") (pintype "passive"))
      (node (ref "U4") (pin "6") (pinfunction "FILTER_6") (pintype "passive"))
    )
    (net (code "92") (name "Net-(U4-VIOUT)") (class "Default")
      (node (ref "R8") (pin "1") (pinfunction "1_1") (pintype "passive"))
      (node (ref "U4") (pin "7") (pinfunction "VIOUT_7") (pintype "passive"))
    )
    (net (code "93") (name "Net-(U6-E)") (class "Default")
      (node (ref "R16") (pin "1") (pinfunction "1_1") (pintype "passive"))
      (node (ref "U6") (pin "3") (pinfunction "E_3") (pintype "passive"))
    )
    (net (code "94") (name "Net-(U6-K)") (class "Default")
      (node (ref "R13") (pin "1") (pinfunction "1_1") (pintype "passive"))
      (node (ref "U6") (pin "2") (pinfunction "K_2") (pintype "passive"))
    )
    (net (code "95") (name "Net-(U7-K)") (class "Default")
      (node (ref "R17") (pin "2") (pinfunction "2_2") (pintype "passive"))
      (node (ref "U7") (pin "2") (pinfunction "K_2") (pintype "passive"))
    )
    (net (code "96") (name "Net-(U8-AVCC)") (class "Default")
      (node (ref "C21") (pin "2") (pinfunction "2_2") (pintype "passive"))
      (node (ref "L5") (pin "1") (pinfunction "1_1") (pintype "passive"))
      (node (ref "U8") (pin "18") (pinfunction "AVCC_18") (pintype "power_in"))
    )
    (net (code "97") (name "Net-(U8-PB6_(PCINT6{slash}XTAL1{slash}TOSC1))") (class "Default")
      (node (ref "C31") (pin "2") (pinfunction "2_2") (pintype "passive"))
      (node (ref "U8") (pin "7") (pinfunction "PB6_(PCINT6/XTAL1/TOSC1)_7") (pintype "bidirectional"))
      (node (ref "Y1") (pin "2") (pinfunction "OSC2_2") (pintype "passive"))
      (node (ref "Y2") (pin "1") (pinfunction "1_1") (pintype "passive"))
    )
    (net (code "98") (name "Net-(U8-PB7_(PCINT7{slash}XTAL2{slash}TOSC2))") (class "Default")
      (node (ref "C30") (pin "2") (pinfunction "2_2") (pintype "passive"))
      (node (ref "U8") (pin "8") (pinfunction "PB7_(PCINT7/XTAL2/TOSC2)_8") (pintype "bidirectional"))
      (node (ref "Y1") (pin "1") (pinfunction "OSC1_1") (pintype "passive"))
      (node (ref "Y2") (pin "3") (pinfunction "3_3") (pintype "passive"))
    )
    (net (code "99") (name "Net-(U9-E)") (class "Default")
      (node (ref "R24") (pin "1") (pinfunction "1_1") (pintype "passive"))
      (node (ref "U9") (pin "3") (pinfunction "E_3") (pintype "passive"))
    )
    (net (code "100") (name "Net-(U9-K)") (class "Default")
      (node (ref "R21") (pin "1") (pinfunction "1_1") (pintype "passive"))
      (node (ref "U9") (pin "2") (pinfunction "K_2") (pintype "passive"))
    )
    (net (code "101") (name "Net-(U10-FILTER)") (class "Default")
      (node (ref "C27") (pin "2") (pinfunction "2_2") (pintype "passive"))
      (node (ref "U10") (pin "6") (pinfunction "FILTER_6") (pintype "passive"))
    )
    (net (code "102") (name "Net-(U10-VIOUT)") (class "Default")
      (node (ref "R28") (pin "1") (pinfunction "1_1") (pintype "passive"))
      (node (ref "U10") (pin "7") (pinfunction "VIOUT_7") (pintype "passive"))
    )
    (net (code "103") (name "Net-(U11-A7)") (class "Default")
      (node (ref "R38") (pin "2") (pinfunction "2_2") (pintype "passive"))
      (node (ref "U11") (pin "9") (pinfunction "A7_9") (pintype "passive"))
    )
    (net (code "104") (name "Net-(U11-B7)") (class "Default")
      (node (ref "R39") (pin "1") (pinfunction "1_1") (pintype "passive"))
      (node (ref "U11") (pin "11") (pinfunction "B7_11") (pintype "passive"))
    )
    (net (code "105") (name "Net-(U12-E)") (class "Default")
      (node (ref "R34") (pin "1") (pinfunction "1_1") (pintype "passive"))
      (node (ref "U12") (pin "3") (pinfunction "E_3") (pintype "passive"))
    )
    (net (code "106") (name "Net-(U12-K)") (class "Default")
      (node (ref "R32") (pin "1") (pinfunction "1_1") (pintype "passive"))
      (node (ref "U12") (pin "2") (pinfunction "K_2") (pintype "passive"))
    )
    (net (code "107") (name "Net-(U13-K)") (class "Default")
      (node (ref "R40") (pin "2") (pinfunction "2_2") (pintype "passive"))
      (node (ref "U13") (pin "2") (pinfunction "K_2") (pintype "passive"))
    )
    (net (code "108") (name "Net-(U14-E)") (class "Default")
      (node (ref "R45") (pin "1") (pinfunction "1_1") (pintype "passive"))
      (node (ref "U14") (pin "3") (pinfunction "E_3") (pintype "passive"))
    )
    (net (code "109") (name "Net-(U14-K)") (class "Default")
      (node (ref "R44") (pin "1") (pinfunction "1_1") (pintype "passive"))
      (node (ref "U14") (pin "2") (pinfunction "K_2") (pintype "passive"))
    )
    (net (code "110") (name "Net-(U15-FILTER)") (class "Default")
      (node (ref "C37") (pin "2") (pinfunction "2_2") (pintype "passive"))
      (node (ref "U15") (pin "6") (pinfunction "FILTER_6") (pintype "passive"))
    )
    (net (code "111") (name "Net-(U15-VIOUT)") (class "Default")
      (node (ref "R46") (pin "1") (pinfunction "1_1") (pintype "passive"))
      (node (ref "U15") (pin "7") (pinfunction "VIOUT_7") (pintype "passive"))
    )
    (net (code "112") (name "Net-(U16-E)") (class "Default")
      (node (ref "R48") (pin "1") (pinfunction "1_1") (pintype "passive"))
      (node (ref "U16") (pin "3") (pinfunction "E_3") (pintype "passive"))
    )
    (net (code "113") (name "Net-(U16-K)") (class "Default")
      (node (ref "R47") (pin "1") (pinfunction "1_1") (pintype "passive"))
      (node (ref "U16") (pin "2") (pinfunction "K_2") (pintype "passive"))
    )
    (net (code "114") (name "Net-(U17-K)") (class "Default")
      (node (ref "R49") (pin "2") (pinfunction "2_2") (pintype "passive"))
      (node (ref "U17") (pin "2") (pinfunction "K_2") (pintype "passive"))
    )
    (net (code "115") (name "Net-(U301-Vin)") (class "Default")
      (node (ref "C3") (pin "1") (pinfunction "1_1") (pintype "passive"))
      (node (ref "C4") (pin "1") (pinfunction "1_1") (pintype "passive"))
      (node (ref "C5") (pin "1") (pinfunction "1_1") (pintype "passive"))
      (node (ref "C9") (pin "1") (pinfunction "1_1") (pintype "passive"))
      (node (ref "L1") (pin "2") (pinfunction "2_2") (pintype "passive"))
      (node (ref "U301") (pin "1") (pinfunction "Vin_1") (pintype "power_in"))
    )
    (net (code "116") (name "Net-(U301-Vout)") (class "Default")
      (node (ref "L301") (pin "1") (pinfunction "1_1") (pintype "passive"))
      (node (ref "U301") (pin "3") (pinfunction "Vout_3") (pintype "passive"))
    )
    (net (code "117") (name "VDD") (class "Default")
      (node (ref "C19") (pin "1") (pinfunction "1_1") (pintype "passive"))
      (node (ref "C201") (pin "1") (pinfunction "1_1") (pintype "passive"))
      (node (ref "C202") (pin "1") (pinfunction "1_1") (pintype "passive"))
      (node (ref "CN1") (pin "2") (pinfunction "2_2") (pintype "passive"))
      (node (ref "L4") (pin "1") (pinfunction "1_1") (pintype "passive"))
      (node (ref "L5") (pin "2") (pinfunction "2_2") (pintype "passive"))
      (node (ref "P5") (pin "3") (pinfunction "3_3") (pintype "passive"))
      (node (ref "R10") (pin "2") (pinfunction "2_2") (pintype "passive"))
      (node (ref "R11") (pin "2") (pinfunction "2_2") (pintype "passive"))
      (node (ref "R14") (pin "2") (pinfunction "2_2") (pintype "passive"))
      (node (ref "R29") (pin "2") (pinfunction "2_2") (pintype "passive"))
      (node (ref "U8") (pin "4") (pinfunction "VCC_4") (pintype "power_in"))
      (node (ref "U8") (pin "6") (pinfunction "VCC_6") (pintype "power_in"))
    )
    (net (code "118") (name "unconnected-(U11-A6-Pad8)") (class "Default")
      (node (ref "U11") (pin "8") (pinfunction "A6_8") (pintype "passive"))
    )
    (net (code "119") (name "unconnected-(U11-B6-Pad12)") (class "Default")
      (node (ref "U11") (pin "12") (pinfunction "B6_12") (pintype "passive"))
    )
  )
)
